# piezo-driver_v0_9b-R001.net
KiCad netlist of a schematic drawn in EAGLE
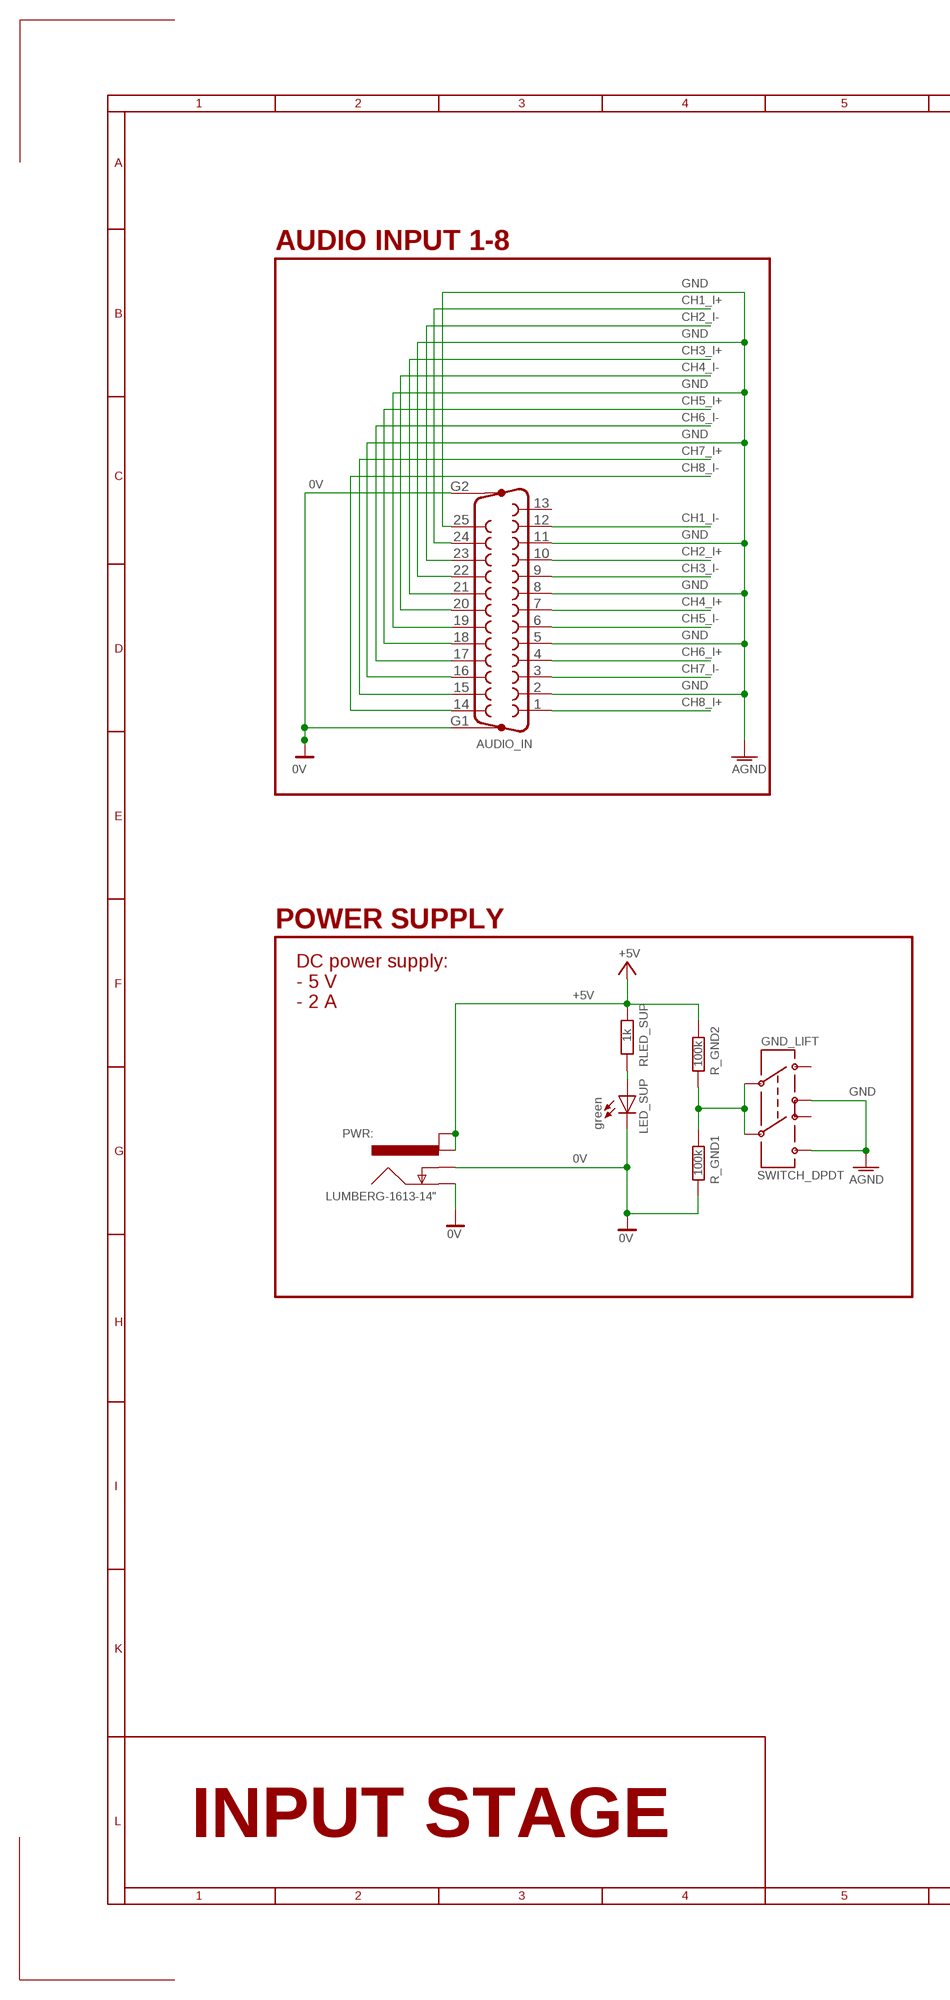
[diagram p0: schematic, sheet 1, part 1 of 2]
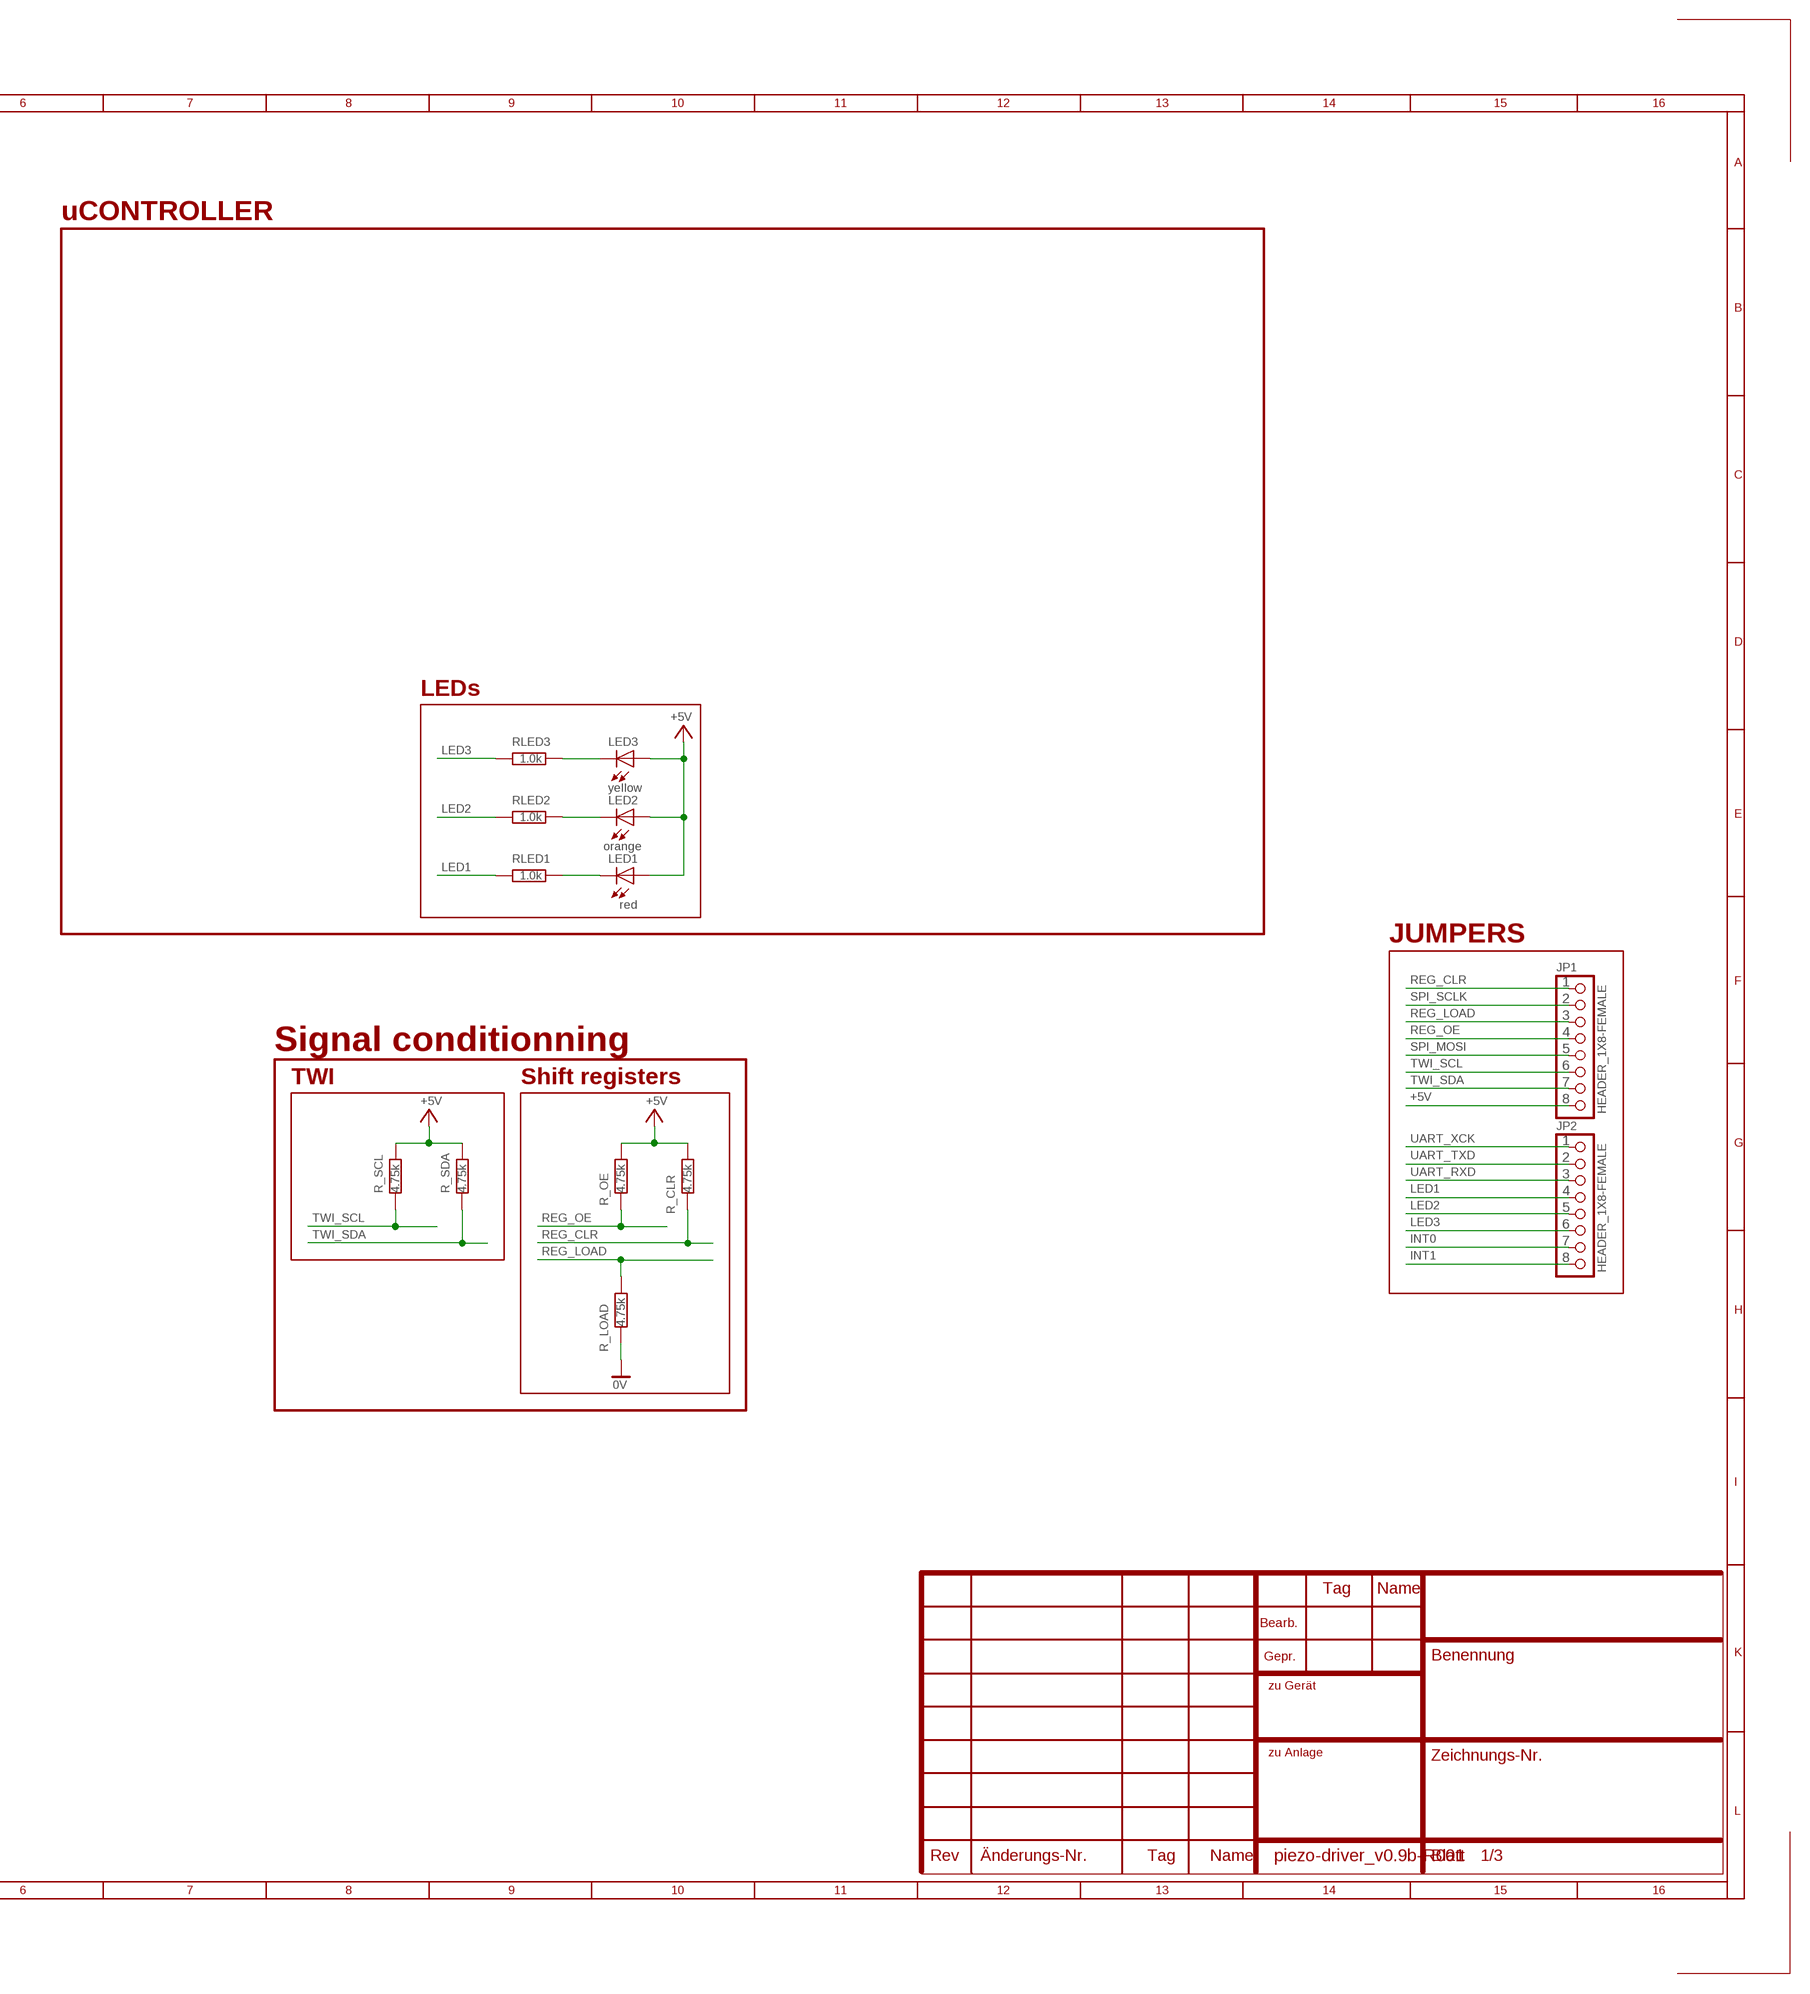
[diagram p1: schematic, sheet 1, part 2 of 2]
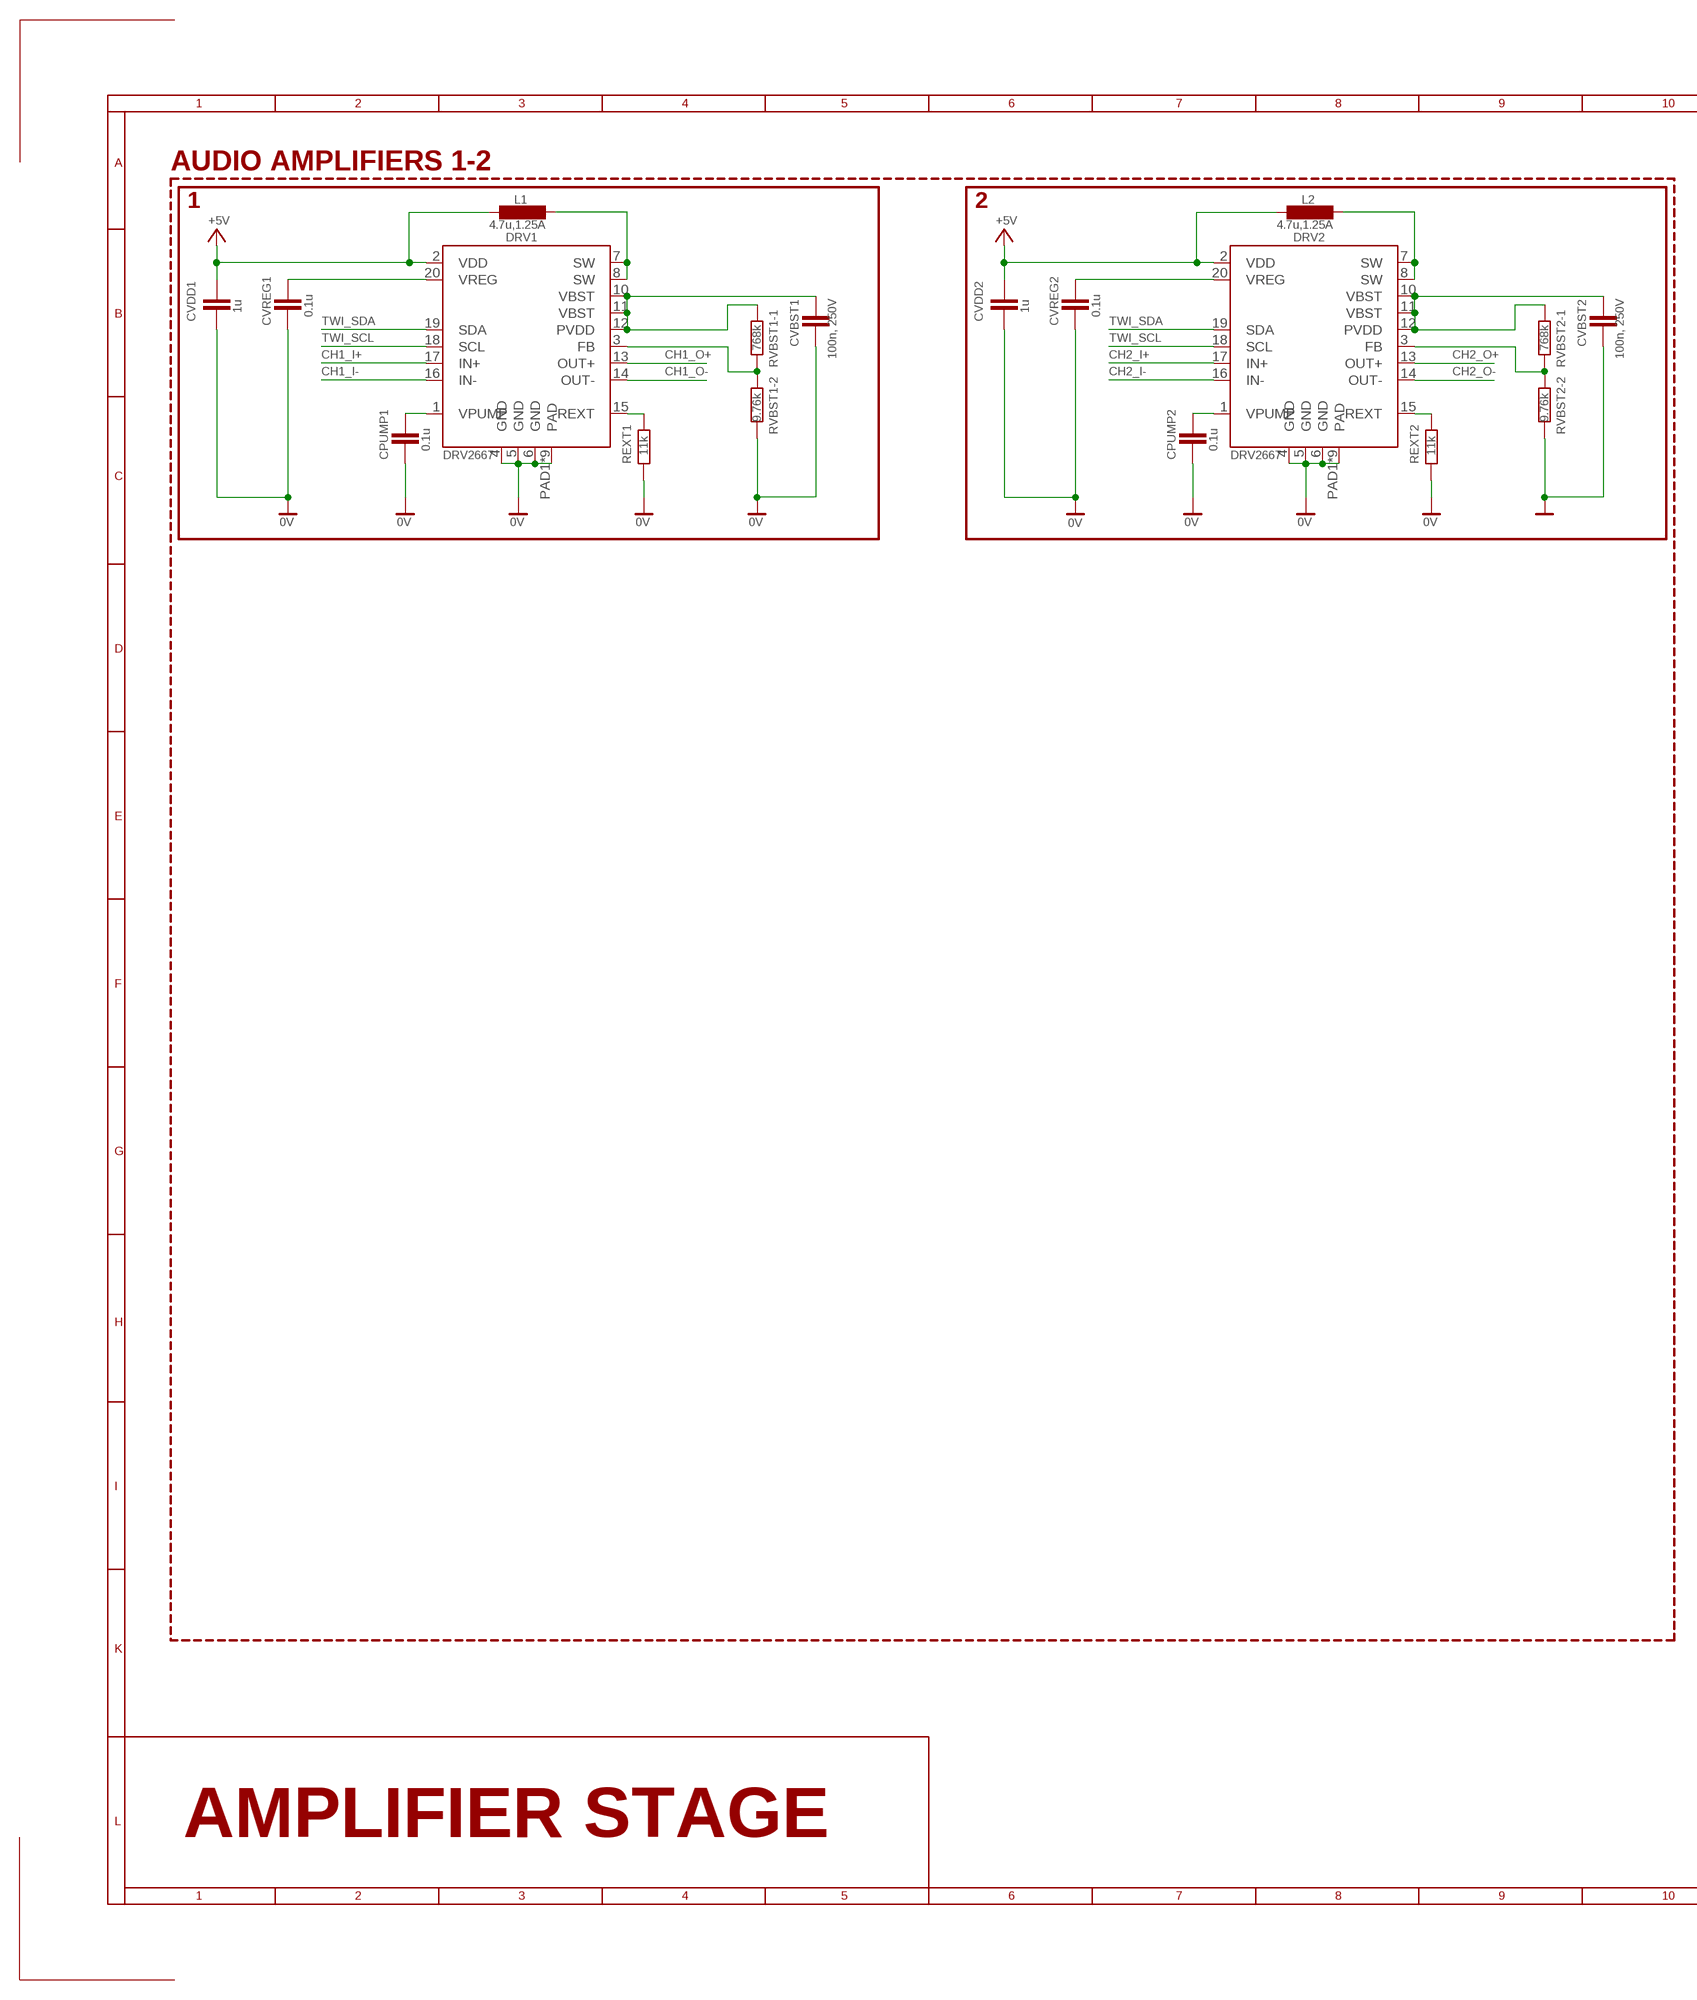
[diagram p2: schematic, sheet 2, part 1 of 2]
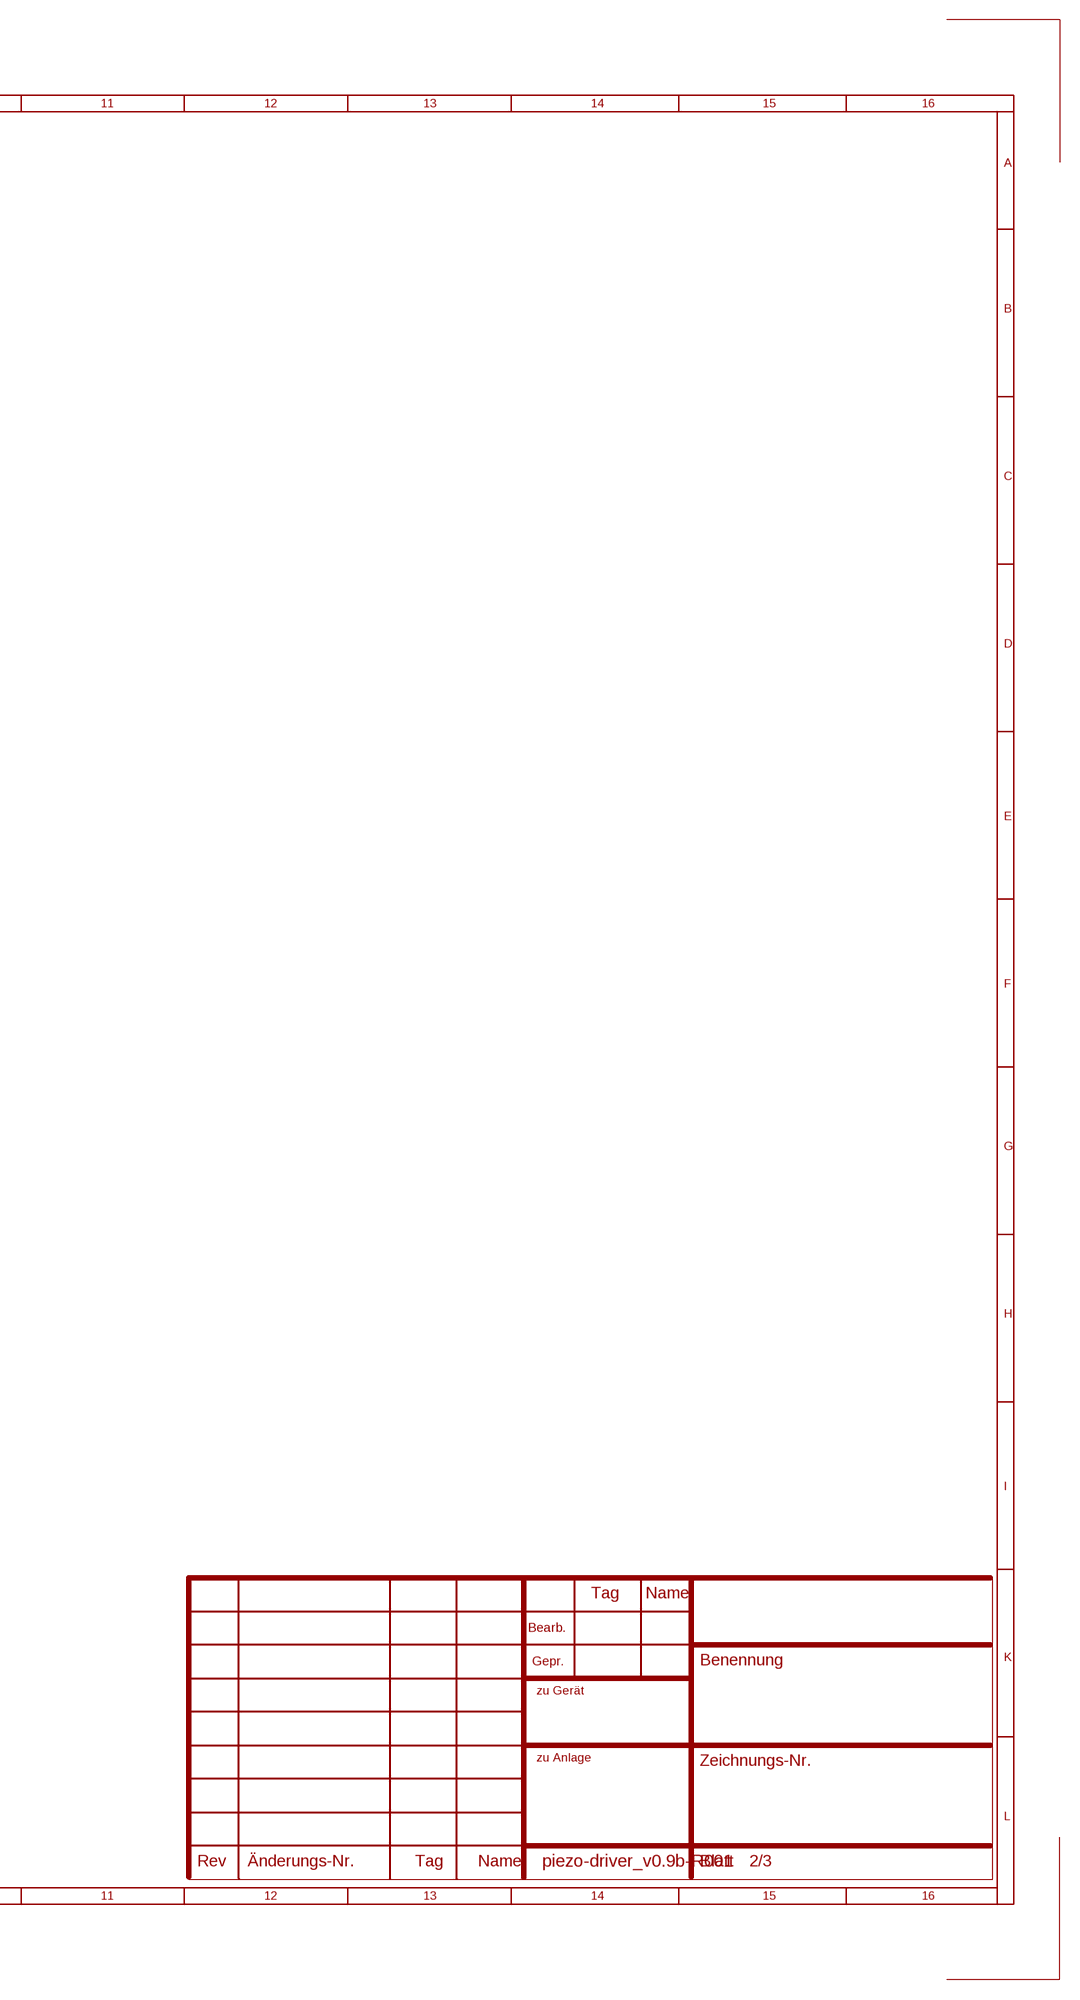
[diagram p3: schematic, sheet 2, part 2 of 2]
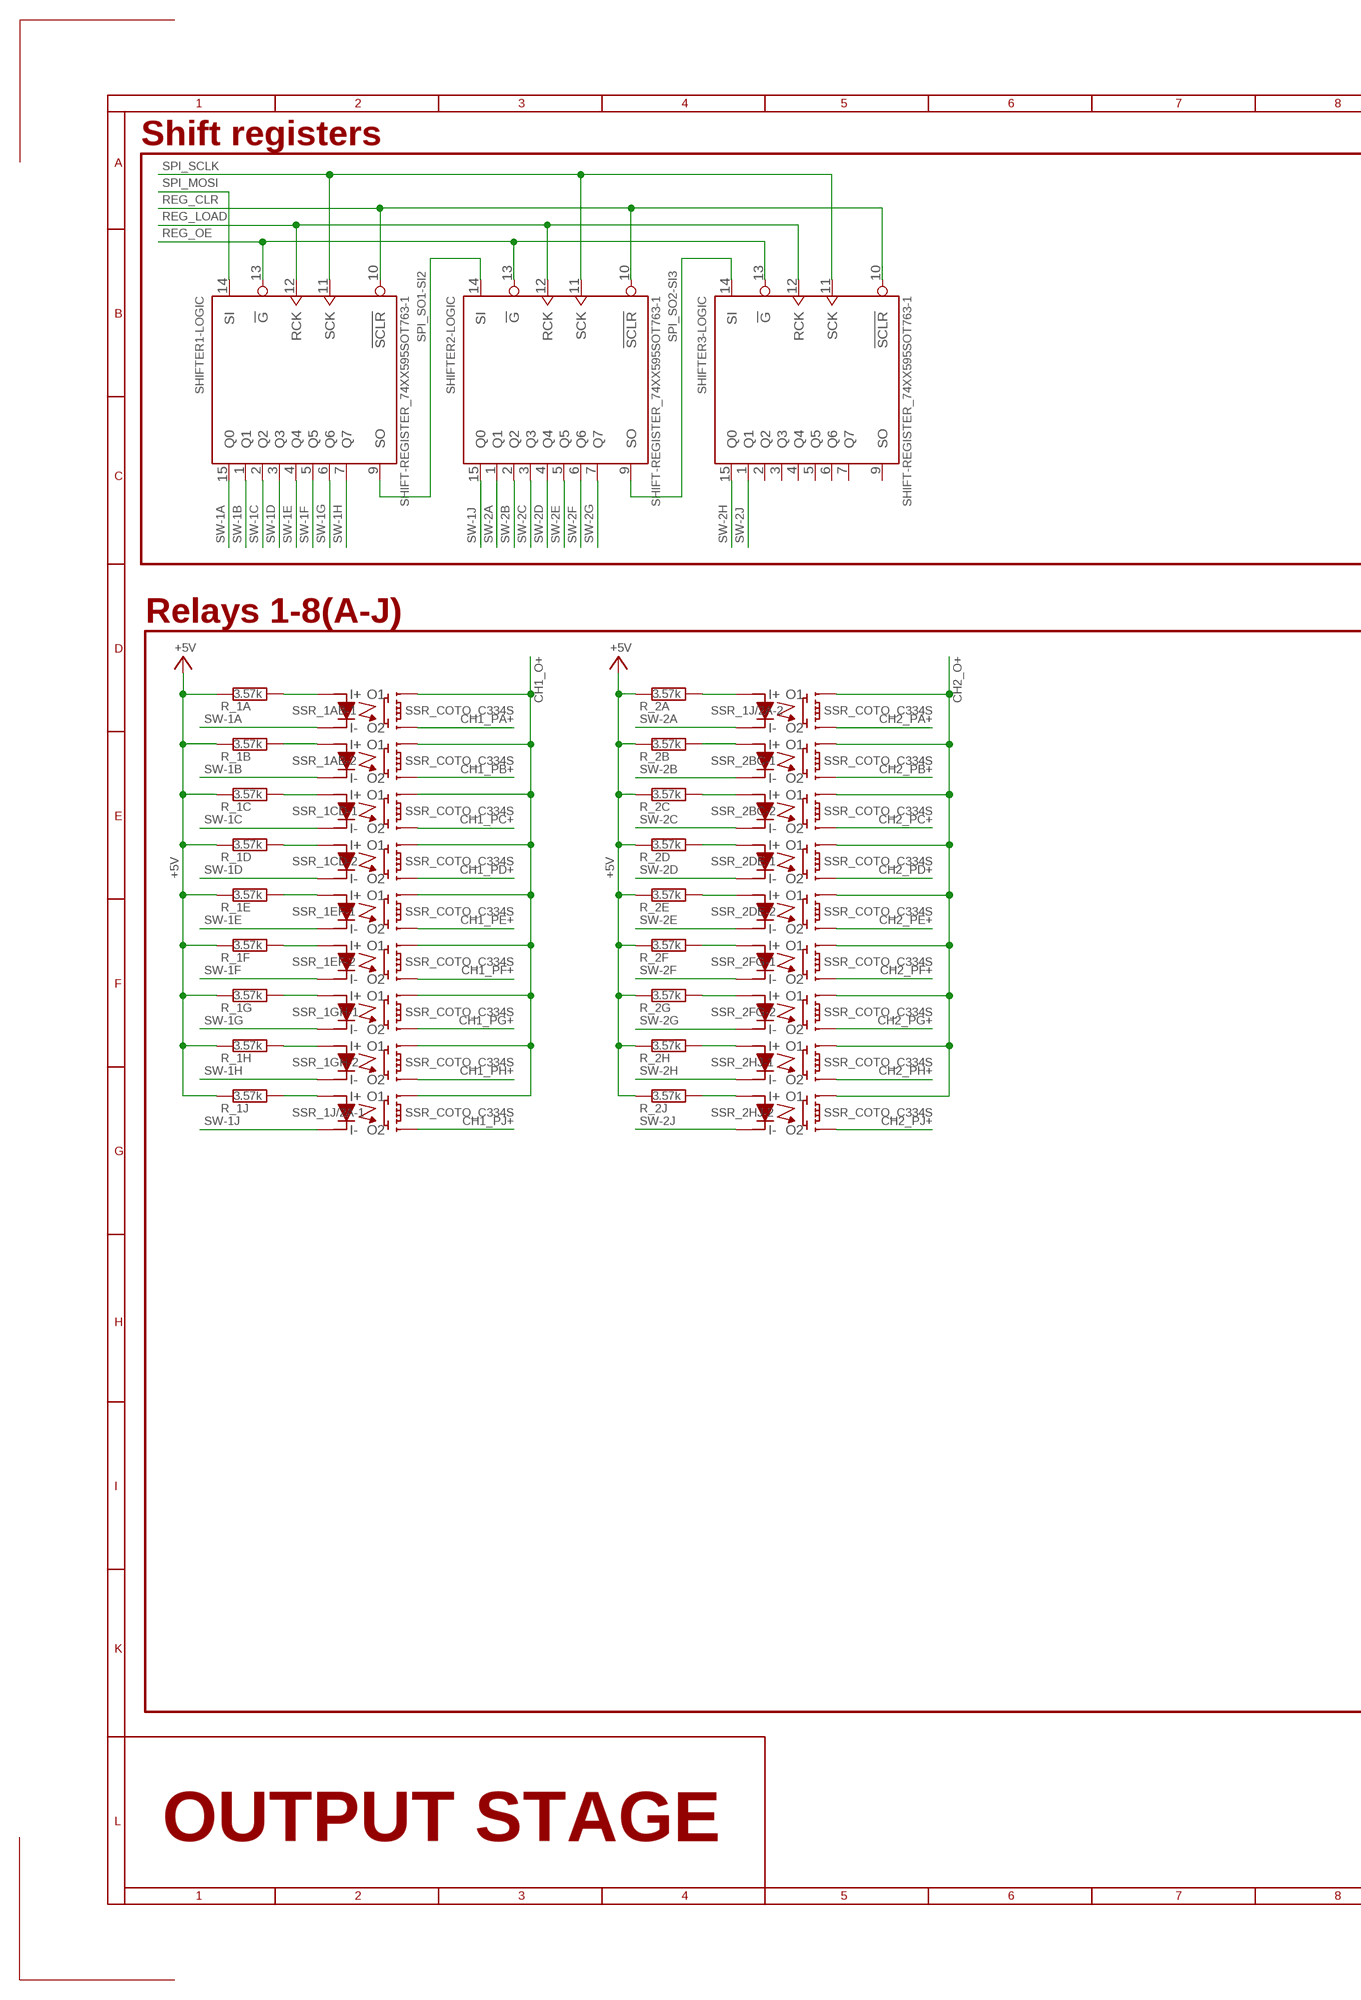
[diagram p4: schematic, sheet 3, part 1 of 2]
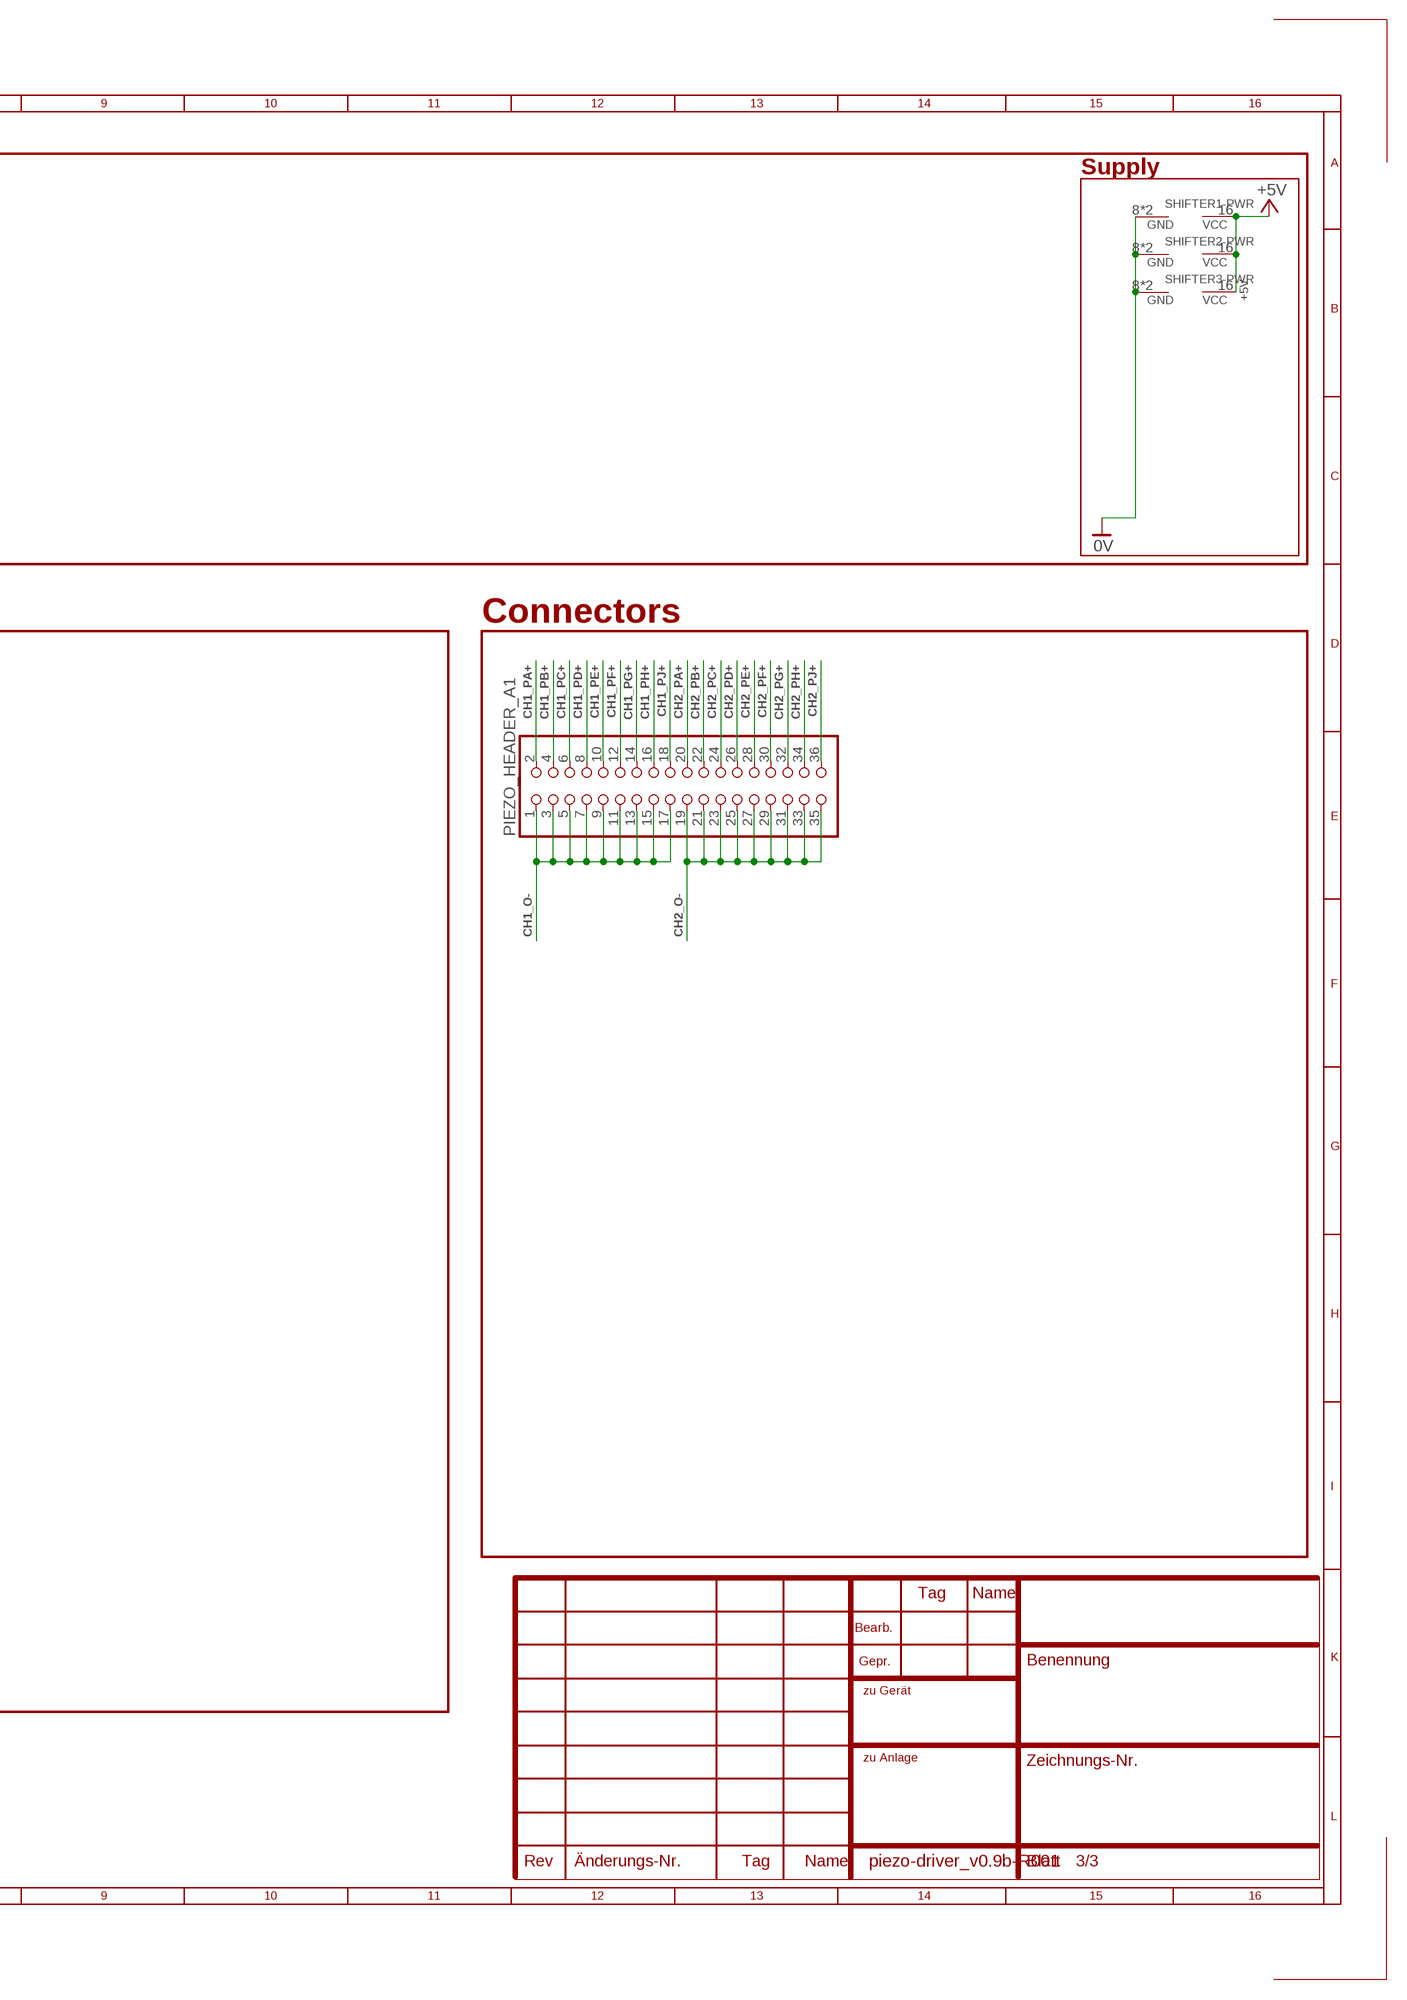
[diagram p5: schematic, sheet 3, part 2 of 2]

(export (version "E")
  (design (tool "Eeschema 10.0.6"))
  (components
    (comp (ref "CPUMP1")
      (value "0.1u")
      (footprint "eagle-import:C0402")
      (libsource (lib "eagle-import") (part "C-EUC0402"))
    )
    (comp (ref "CPUMP2")
      (value "0.1u")
      (footprint "eagle-import:C0402")
      (libsource (lib "eagle-import") (part "C-EUC0402"))
    )
    (comp (ref "CVBST1")
      (value "100n, 250V")
      (footprint "eagle-import:C0805")
      (libsource (lib "eagle-import") (part "C-EUC0805"))
    )
    (comp (ref "CVBST2")
      (value "100n, 250V")
      (footprint "eagle-import:C0805")
      (libsource (lib "eagle-import") (part "C-EUC0805"))
    )
    (comp (ref "CVDD1")
      (value "1u")
      (footprint "eagle-import:C0402")
      (libsource (lib "eagle-import") (part "C-EUC0402"))
    )
    (comp (ref "CVDD2")
      (value "1u")
      (footprint "eagle-import:C0402")
      (libsource (lib "eagle-import") (part "C-EUC0402"))
    )
    (comp (ref "CVREG1")
      (value "0.1u")
      (footprint "eagle-import:C0402")
      (libsource (lib "eagle-import") (part "C-EUC0402"))
    )
    (comp (ref "CVREG2")
      (value "0.1u")
      (footprint "eagle-import:C0402")
      (libsource (lib "eagle-import") (part "C-EUC0402"))
    )
    (comp (ref "DRV1")
      (value "DRV2667")
      (footprint "eagle-import:QFN-20_9TH")
      (libsource (lib "eagle-import") (part "DRV2667"))
    )
    (comp (ref "DRV2")
      (value "DRV2667")
      (footprint "eagle-import:QFN-20_9TH")
      (libsource (lib "eagle-import") (part "DRV2667"))
    )
    (comp (ref "L1")
      (value "4.7u,1.25A")
      (footprint "eagle-import:L3030")
      (libsource (lib "eagle-import") (part "L-EUL3030"))
    )
    (comp (ref "L2")
      (value "4.7u,1.25A")
      (footprint "eagle-import:L3030")
      (libsource (lib "eagle-import") (part "L-EUL3030"))
    )
    (comp (ref "REXT1")
      (value "11k")
      (footprint "eagle-import:R0402")
      (libsource (lib "eagle-import") (part "R-EU_R0402"))
    )
    (comp (ref "REXT2")
      (value "11k")
      (footprint "eagle-import:R0402")
      (libsource (lib "eagle-import") (part "R-EU_R0402"))
    )
    (comp (ref "RVBST1-1")
      (value "768k")
      (footprint "eagle-import:R0402")
      (libsource (lib "eagle-import") (part "R-EU_R0402"))
    )
    (comp (ref "RVBST1-2")
      (value "9.76k")
      (footprint "eagle-import:R0402")
      (libsource (lib "eagle-import") (part "R-EU_R0402"))
    )
    (comp (ref "RVBST2-1")
      (value "768k")
      (footprint "eagle-import:R0402")
      (libsource (lib "eagle-import") (part "R-EU_R0402"))
    )
    (comp (ref "RVBST2-2")
      (value "9.76k")
      (footprint "eagle-import:R0402")
      (libsource (lib "eagle-import") (part "R-EU_R0402"))
    )
    (comp (ref "AUDIO_IN")
      (value "F25HP")
      (footprint "eagle-import:F25HP")
      (libsource (lib "eagle-import") (part "F25HP"))
    )
    (comp (ref "GND_LIFT")
      (value "SWITCH_DPDT")
      (footprint "eagle-import:SWITCH_JS202011")
      (libsource (lib "eagle-import") (part "SWITCH_DPDT"))
    )
    (comp (ref "JP1")
      (value "HEADER_1X8-FEMALE")
      (footprint "eagle-import:1X08_2.54")
      (libsource (lib "eagle-import") (part "HEADER_1X8-FEMALE"))
    )
    (comp (ref "JP2")
      (value "HEADER_1X8-FEMALE")
      (footprint "eagle-import:1X08_2.54")
      (libsource (lib "eagle-import") (part "HEADER_1X8-FEMALE"))
    )
    (comp (ref "LED1")
      (value "red")
      (footprint "eagle-import:LED-1206")
      (libsource (lib "eagle-import") (part "LED1206"))
    )
    (comp (ref "LED2")
      (value "orange")
      (footprint "eagle-import:LED-1206")
      (libsource (lib "eagle-import") (part "LED1206"))
    )
    (comp (ref "LED3")
      (value "yellow")
      (footprint "eagle-import:LED-1206")
      (libsource (lib "eagle-import") (part "LED1206"))
    )
    (comp (ref "LED_SUP")
      (value "green")
      (footprint "eagle-import:LED-1206")
      (libsource (lib "eagle-import") (part "LED1206"))
    )
    (comp (ref "PWR:")
      (value "LUMBERG-1613-14\"")
      (footprint "eagle-import:LUMBERG-1613_14")
      (libsource (lib "eagle-import") (part "LUMBERG-1613-14{dblquote}"))
    )
    (comp (ref "RLED1")
      (value "1.0k")
      (footprint "eagle-import:R0402")
      (libsource (lib "eagle-import") (part "R-EU_R0402"))
    )
    (comp (ref "RLED2")
      (value "1.0k")
      (footprint "eagle-import:R0402")
      (libsource (lib "eagle-import") (part "R-EU_R0402"))
    )
    (comp (ref "RLED3")
      (value "1.0k")
      (footprint "eagle-import:R0402")
      (libsource (lib "eagle-import") (part "R-EU_R0402"))
    )
    (comp (ref "RLED_SUP")
      (value "1k")
      (footprint "eagle-import:R0402")
      (libsource (lib "eagle-import") (part "R-EU_R0402"))
    )
    (comp (ref "R_CLR")
      (value "4.75k")
      (footprint "eagle-import:R0402")
      (libsource (lib "eagle-import") (part "R-EU_R0402"))
    )
    (comp (ref "R_GND1")
      (value "100k")
      (footprint "eagle-import:R0402")
      (libsource (lib "eagle-import") (part "R-EU_R0402"))
    )
    (comp (ref "R_GND2")
      (value "100k")
      (footprint "eagle-import:R0402")
      (libsource (lib "eagle-import") (part "R-EU_R0402"))
    )
    (comp (ref "R_LOAD")
      (value "4.75k")
      (footprint "eagle-import:R0402")
      (libsource (lib "eagle-import") (part "R-EU_R0402"))
    )
    (comp (ref "R_OE")
      (value "4.75k")
      (footprint "eagle-import:R0402")
      (libsource (lib "eagle-import") (part "R-EU_R0402"))
    )
    (comp (ref "R_SCL")
      (value "4.75k")
      (footprint "eagle-import:R0402")
      (libsource (lib "eagle-import") (part "R-EU_R0402"))
    )
    (comp (ref "R_SDA")
      (value "4.75k")
      (footprint "eagle-import:R0402")
      (libsource (lib "eagle-import") (part "R-EU_R0402"))
    )
    (comp (ref "PIEZO_HEADER_A1")
      (value "PINHD-2X18")
      (footprint "eagle-import:2X18")
      (libsource (lib "eagle-import") (part "PINHD-2X18"))
    )
    (comp (ref "R_1A")
      (value "3.57k")
      (footprint "eagle-import:R0402")
      (libsource (lib "eagle-import") (part "R-EU_R0402"))
    )
    (comp (ref "R_1B")
      (value "3.57k")
      (footprint "eagle-import:R0402")
      (libsource (lib "eagle-import") (part "R-EU_R0402"))
    )
    (comp (ref "R_1C")
      (value "3.57k")
      (footprint "eagle-import:R0402")
      (libsource (lib "eagle-import") (part "R-EU_R0402"))
    )
    (comp (ref "R_1D")
      (value "3.57k")
      (footprint "eagle-import:R0402")
      (libsource (lib "eagle-import") (part "R-EU_R0402"))
    )
    (comp (ref "R_1E")
      (value "3.57k")
      (footprint "eagle-import:R0402")
      (libsource (lib "eagle-import") (part "R-EU_R0402"))
    )
    (comp (ref "R_1F")
      (value "3.57k")
      (footprint "eagle-import:R0402")
      (libsource (lib "eagle-import") (part "R-EU_R0402"))
    )
    (comp (ref "R_1G")
      (value "3.57k")
      (footprint "eagle-import:R0402")
      (libsource (lib "eagle-import") (part "R-EU_R0402"))
    )
    (comp (ref "R_1H")
      (value "3.57k")
      (footprint "eagle-import:R0402")
      (libsource (lib "eagle-import") (part "R-EU_R0402"))
    )
    (comp (ref "R_1J")
      (value "3.57k")
      (footprint "eagle-import:R0402")
      (libsource (lib "eagle-import") (part "R-EU_R0402"))
    )
    (comp (ref "R_2A")
      (value "3.57k")
      (footprint "eagle-import:R0402")
      (libsource (lib "eagle-import") (part "R-EU_R0402"))
    )
    (comp (ref "R_2B")
      (value "3.57k")
      (footprint "eagle-import:R0402")
      (libsource (lib "eagle-import") (part "R-EU_R0402"))
    )
    (comp (ref "R_2C")
      (value "3.57k")
      (footprint "eagle-import:R0402")
      (libsource (lib "eagle-import") (part "R-EU_R0402"))
    )
    (comp (ref "R_2D")
      (value "3.57k")
      (footprint "eagle-import:R0402")
      (libsource (lib "eagle-import") (part "R-EU_R0402"))
    )
    (comp (ref "R_2E")
      (value "3.57k")
      (footprint "eagle-import:R0402")
      (libsource (lib "eagle-import") (part "R-EU_R0402"))
    )
    (comp (ref "R_2F")
      (value "3.57k")
      (footprint "eagle-import:R0402")
      (libsource (lib "eagle-import") (part "R-EU_R0402"))
    )
    (comp (ref "R_2G")
      (value "3.57k")
      (footprint "eagle-import:R0402")
      (libsource (lib "eagle-import") (part "R-EU_R0402"))
    )
    (comp (ref "R_2H")
      (value "3.57k")
      (footprint "eagle-import:R0402")
      (libsource (lib "eagle-import") (part "R-EU_R0402"))
    )
    (comp (ref "R_2J")
      (value "3.57k")
      (footprint "eagle-import:R0402")
      (libsource (lib "eagle-import") (part "R-EU_R0402"))
    )
    (comp (ref "SHIFTER1")
      (value "SHIFT-REGISTER_74XX595SOT763-1")
      (footprint "eagle-import:SOT763-1")
      (libsource (lib "eagle-import") (part "SHIFT-REGISTER_74XX595SOT763-1"))
    )
    (comp (ref "SHIFTER2")
      (value "SHIFT-REGISTER_74XX595SOT763-1")
      (footprint "eagle-import:SOT763-1")
      (libsource (lib "eagle-import") (part "SHIFT-REGISTER_74XX595SOT763-1"))
    )
    (comp (ref "SHIFTER3")
      (value "SHIFT-REGISTER_74XX595SOT763-1")
      (footprint "eagle-import:SOT763-1")
      (libsource (lib "eagle-import") (part "SHIFT-REGISTER_74XX595SOT763-1"))
    )
    (comp (ref "SSR_1AB")
      (value "SSR_COTO_C334S")
      (footprint "eagle-import:SOP8")
      (libsource (lib "eagle-import") (part "SSR_COTO_C334S"))
    )
    (comp (ref "SSR_1CD")
      (value "SSR_COTO_C334S")
      (footprint "eagle-import:SOP8")
      (libsource (lib "eagle-import") (part "SSR_COTO_C334S"))
    )
    (comp (ref "SSR_1EF")
      (value "SSR_COTO_C334S")
      (footprint "eagle-import:SOP8")
      (libsource (lib "eagle-import") (part "SSR_COTO_C334S"))
    )
    (comp (ref "SSR_1GH")
      (value "SSR_COTO_C334S")
      (footprint "eagle-import:SOP8")
      (libsource (lib "eagle-import") (part "SSR_COTO_C334S"))
    )
    (comp (ref "SSR_1J/2A")
      (value "SSR_COTO_C334S")
      (footprint "eagle-import:SOP8")
      (libsource (lib "eagle-import") (part "SSR_COTO_C334S"))
    )
    (comp (ref "SSR_2BC")
      (value "SSR_COTO_C334S")
      (footprint "eagle-import:SOP8")
      (libsource (lib "eagle-import") (part "SSR_COTO_C334S"))
    )
    (comp (ref "SSR_2DE")
      (value "SSR_COTO_C334S")
      (footprint "eagle-import:SOP8")
      (libsource (lib "eagle-import") (part "SSR_COTO_C334S"))
    )
    (comp (ref "SSR_2FG")
      (value "SSR_COTO_C334S")
      (footprint "eagle-import:SOP8")
      (libsource (lib "eagle-import") (part "SSR_COTO_C334S"))
    )
    (comp (ref "SSR_2HJ")
      (value "SSR_COTO_C334S")
      (footprint "eagle-import:SOP8")
      (libsource (lib "eagle-import") (part "SSR_COTO_C334S"))
    )
  )
  (nets
    (net (code "1") (name "+5V") (class "Default")
      (node (ref "CVDD1") (pin "1") (pinfunction "1_1") (pintype "passive"))
      (node (ref "CVDD2") (pin "1") (pinfunction "1_1") (pintype "passive"))
      (node (ref "DRV1") (pin "2") (pinfunction "VDD_2") (pintype "bidirectional"))
      (node (ref "DRV2") (pin "2") (pinfunction "VDD_2") (pintype "bidirectional"))
      (node (ref "JP1") (pin "8") (pinfunction "8_8") (pintype "passive"))
      (node (ref "L1") (pin "2") (pinfunction "2_2") (pintype "passive"))
      (node (ref "L2") (pin "2") (pinfunction "2_2") (pintype "passive"))
      (node (ref "LED1") (pin "A") (pinfunction "A_A") (pintype "passive"))
      (node (ref "LED2") (pin "A") (pinfunction "A_A") (pintype "passive"))
      (node (ref "LED3") (pin "A") (pinfunction "A_A") (pintype "passive"))
      (node (ref "PWR:") (pin "3") (pinfunction "PWR_1_3") (pintype "power_in"))
      (node (ref "PWR:") (pin "4") (pinfunction "PWR_2_4") (pintype "power_in"))
      (node (ref "RLED_SUP") (pin "2") (pinfunction "2_2") (pintype "passive"))
      (node (ref "R_1A") (pin "2") (pinfunction "2_2") (pintype "passive"))
      (node (ref "R_1B") (pin "2") (pinfunction "2_2") (pintype "passive"))
      (node (ref "R_1C") (pin "2") (pinfunction "2_2") (pintype "passive"))
      (node (ref "R_1D") (pin "2") (pinfunction "2_2") (pintype "passive"))
      (node (ref "R_1E") (pin "2") (pinfunction "2_2") (pintype "passive"))
      (node (ref "R_1F") (pin "2") (pinfunction "2_2") (pintype "passive"))
      (node (ref "R_1G") (pin "2") (pinfunction "2_2") (pintype "passive"))
      (node (ref "R_1H") (pin "2") (pinfunction "2_2") (pintype "passive"))
      (node (ref "R_1J") (pin "2") (pinfunction "2_2") (pintype "passive"))
      (node (ref "R_2A") (pin "2") (pinfunction "2_2") (pintype "passive"))
      (node (ref "R_2B") (pin "2") (pinfunction "2_2") (pintype "passive"))
      (node (ref "R_2C") (pin "2") (pinfunction "2_2") (pintype "passive"))
      (node (ref "R_2D") (pin "2") (pinfunction "2_2") (pintype "passive"))
      (node (ref "R_2E") (pin "2") (pinfunction "2_2") (pintype "passive"))
      (node (ref "R_2F") (pin "2") (pinfunction "2_2") (pintype "passive"))
      (node (ref "R_2G") (pin "2") (pinfunction "2_2") (pintype "passive"))
      (node (ref "R_2H") (pin "2") (pinfunction "2_2") (pintype "passive"))
      (node (ref "R_2J") (pin "2") (pinfunction "2_2") (pintype "passive"))
      (node (ref "R_CLR") (pin "2") (pinfunction "2_2") (pintype "passive"))
      (node (ref "R_GND2") (pin "2") (pinfunction "2_2") (pintype "passive"))
      (node (ref "R_OE") (pin "2") (pinfunction "2_2") (pintype "passive"))
      (node (ref "R_SCL") (pin "2") (pinfunction "2_2") (pintype "passive"))
      (node (ref "R_SDA") (pin "2") (pinfunction "2_2") (pintype "passive"))
      (node (ref "SHIFTER1") (pin "16") (pinfunction "VCC_16") (pintype "power_in"))
      (node (ref "SHIFTER2") (pin "16") (pinfunction "VCC_16") (pintype "power_in"))
      (node (ref "SHIFTER3") (pin "16") (pinfunction "VCC_16") (pintype "power_in"))
    )
    (net (code "2") (name "0V") (class "Default")
      (node (ref "AUDIO_IN") (pin "G1") (pinfunction "G1_G1") (pintype "passive"))
      (node (ref "AUDIO_IN") (pin "G2") (pinfunction "G2_G2") (pintype "passive"))
      (node (ref "CPUMP1") (pin "2") (pinfunction "2_2") (pintype "passive"))
      (node (ref "CPUMP2") (pin "2") (pinfunction "2_2") (pintype "passive"))
      (node (ref "CVBST1") (pin "2") (pinfunction "2_2") (pintype "passive"))
      (node (ref "CVBST2") (pin "2") (pinfunction "2_2") (pintype "passive"))
      (node (ref "CVDD1") (pin "2") (pinfunction "2_2") (pintype "passive"))
      (node (ref "CVDD2") (pin "2") (pinfunction "2_2") (pintype "passive"))
      (node (ref "CVREG1") (pin "2") (pinfunction "2_2") (pintype "passive"))
      (node (ref "CVREG2") (pin "2") (pinfunction "2_2") (pintype "passive"))
      (node (ref "DRV1") (pin "4") (pinfunction "GND_4") (pintype "bidirectional"))
      (node (ref "DRV1") (pin "5") (pinfunction "GND_5") (pintype "bidirectional"))
      (node (ref "DRV1") (pin "6") (pinfunction "GND_6") (pintype "bidirectional"))
      (node (ref "DRV1") (pin "PAD1") (pinfunction "PAD_PAD1") (pintype "bidirectional"))
      (node (ref "DRV1") (pin "PAD2") (pinfunction "PAD_PAD2") (pintype "bidirectional"))
      (node (ref "DRV1") (pin "PAD3") (pinfunction "PAD_PAD3") (pintype "bidirectional"))
      (node (ref "DRV1") (pin "PAD4") (pinfunction "PAD_PAD4") (pintype "bidirectional"))
      (node (ref "DRV1") (pin "PAD5") (pinfunction "PAD_PAD5") (pintype "bidirectional"))
      (node (ref "DRV1") (pin "PAD6") (pinfunction "PAD_PAD6") (pintype "bidirectional"))
      (node (ref "DRV1") (pin "PAD7") (pinfunction "PAD_PAD7") (pintype "bidirectional"))
      (node (ref "DRV1") (pin "PAD8") (pinfunction "PAD_PAD8") (pintype "bidirectional"))
      (node (ref "DRV1") (pin "PAD9") (pinfunction "PAD_PAD9") (pintype "bidirectional"))
      (node (ref "DRV2") (pin "4") (pinfunction "GND_4") (pintype "bidirectional"))
      (node (ref "DRV2") (pin "5") (pinfunction "GND_5") (pintype "bidirectional"))
      (node (ref "DRV2") (pin "6") (pinfunction "GND_6") (pintype "bidirectional"))
      (node (ref "DRV2") (pin "PAD1") (pinfunction "PAD_PAD1") (pintype "bidirectional"))
      (node (ref "DRV2") (pin "PAD2") (pinfunction "PAD_PAD2") (pintype "bidirectional"))
      (node (ref "DRV2") (pin "PAD3") (pinfunction "PAD_PAD3") (pintype "bidirectional"))
      (node (ref "DRV2") (pin "PAD4") (pinfunction "PAD_PAD4") (pintype "bidirectional"))
      (node (ref "DRV2") (pin "PAD5") (pinfunction "PAD_PAD5") (pintype "bidirectional"))
      (node (ref "DRV2") (pin "PAD6") (pinfunction "PAD_PAD6") (pintype "bidirectional"))
      (node (ref "DRV2") (pin "PAD7") (pinfunction "PAD_PAD7") (pintype "bidirectional"))
      (node (ref "DRV2") (pin "PAD8") (pinfunction "PAD_PAD8") (pintype "bidirectional"))
      (node (ref "DRV2") (pin "PAD9") (pinfunction "PAD_PAD9") (pintype "bidirectional"))
      (node (ref "LED_SUP") (pin "C") (pinfunction "C_C") (pintype "passive"))
      (node (ref "PWR:") (pin "1") (pinfunction "GND_1") (pintype "power_in"))
      (node (ref "PWR:") (pin "2") (pinfunction "GND_INS_2") (pintype "power_in"))
      (node (ref "REXT1") (pin "1") (pinfunction "1_1") (pintype "passive"))
      (node (ref "REXT2") (pin "1") (pinfunction "1_1") (pintype "passive"))
      (node (ref "RVBST1-2") (pin "1") (pinfunction "1_1") (pintype "passive"))
      (node (ref "RVBST2-2") (pin "1") (pinfunction "1_1") (pintype "passive"))
      (node (ref "R_GND1") (pin "1") (pinfunction "1_1") (pintype "passive"))
      (node (ref "R_LOAD") (pin "1") (pinfunction "1_1") (pintype "passive"))
      (node (ref "SHIFTER1") (pin "8") (pinfunction "GND_8") (pintype "power_in"))
      (node (ref "SHIFTER1") (pin "PAD") (pinfunction "GND_PAD") (pintype "power_in"))
      (node (ref "SHIFTER2") (pin "8") (pinfunction "GND_8") (pintype "power_in"))
      (node (ref "SHIFTER2") (pin "PAD") (pinfunction "GND_PAD") (pintype "power_in"))
      (node (ref "SHIFTER3") (pin "8") (pinfunction "GND_8") (pintype "power_in"))
      (node (ref "SHIFTER3") (pin "PAD") (pinfunction "GND_PAD") (pintype "power_in"))
    )
    (net (code "3") (name "CH1_I+") (class "Default")
      (node (ref "AUDIO_IN") (pin "24") (pinfunction "24_24") (pintype "passive"))
      (node (ref "DRV1") (pin "17") (pinfunction "IN+_17") (pintype "bidirectional"))
    )
    (net (code "4") (name "CH1_I-") (class "Default")
      (node (ref "AUDIO_IN") (pin "12") (pinfunction "12_12") (pintype "passive"))
      (node (ref "DRV1") (pin "16") (pinfunction "IN-_16") (pintype "bidirectional"))
    )
    (net (code "5") (name "CH1_O+") (class "Default")
      (node (ref "DRV1") (pin "13") (pinfunction "OUT+_13") (pintype "bidirectional"))
      (node (ref "SSR_1AB") (pin "5") (pinfunction "O1_5") (pintype "bidirectional"))
      (node (ref "SSR_1AB") (pin "7") (pinfunction "O1_7") (pintype "bidirectional"))
      (node (ref "SSR_1CD") (pin "5") (pinfunction "O1_5") (pintype "bidirectional"))
      (node (ref "SSR_1CD") (pin "7") (pinfunction "O1_7") (pintype "bidirectional"))
      (node (ref "SSR_1EF") (pin "5") (pinfunction "O1_5") (pintype "bidirectional"))
      (node (ref "SSR_1EF") (pin "7") (pinfunction "O1_7") (pintype "bidirectional"))
      (node (ref "SSR_1GH") (pin "5") (pinfunction "O1_5") (pintype "bidirectional"))
      (node (ref "SSR_1GH") (pin "7") (pinfunction "O1_7") (pintype "bidirectional"))
      (node (ref "SSR_1J/2A") (pin "7") (pinfunction "O1_7") (pintype "bidirectional"))
    )
    (net (code "6") (name "CH1_O-") (class "Default")
      (node (ref "DRV1") (pin "14") (pinfunction "OUT-_14") (pintype "bidirectional"))
      (node (ref "PIEZO_HEADER_A1") (pin "1") (pinfunction "1_1") (pintype "passive"))
      (node (ref "PIEZO_HEADER_A1") (pin "11") (pinfunction "11_11") (pintype "passive"))
      (node (ref "PIEZO_HEADER_A1") (pin "13") (pinfunction "13_13") (pintype "passive"))
      (node (ref "PIEZO_HEADER_A1") (pin "15") (pinfunction "15_15") (pintype "passive"))
      (node (ref "PIEZO_HEADER_A1") (pin "17") (pinfunction "17_17") (pintype "passive"))
      (node (ref "PIEZO_HEADER_A1") (pin "3") (pinfunction "3_3") (pintype "passive"))
      (node (ref "PIEZO_HEADER_A1") (pin "5") (pinfunction "5_5") (pintype "passive"))
      (node (ref "PIEZO_HEADER_A1") (pin "7") (pinfunction "7_7") (pintype "passive"))
      (node (ref "PIEZO_HEADER_A1") (pin "9") (pinfunction "9_9") (pintype "passive"))
    )
    (net (code "7") (name "CH1_PA+") (class "Default")
      (node (ref "PIEZO_HEADER_A1") (pin "2") (pinfunction "2_2") (pintype "passive"))
      (node (ref "SSR_1AB") (pin "8") (pinfunction "O2_8") (pintype "bidirectional"))
    )
    (net (code "8") (name "CH1_PB+") (class "Default")
      (node (ref "PIEZO_HEADER_A1") (pin "4") (pinfunction "4_4") (pintype "passive"))
      (node (ref "SSR_1AB") (pin "6") (pinfunction "O2_6") (pintype "bidirectional"))
    )
    (net (code "9") (name "CH1_PC+") (class "Default")
      (node (ref "PIEZO_HEADER_A1") (pin "6") (pinfunction "6_6") (pintype "passive"))
      (node (ref "SSR_1CD") (pin "8") (pinfunction "O2_8") (pintype "bidirectional"))
    )
    (net (code "10") (name "CH1_PD+") (class "Default")
      (node (ref "PIEZO_HEADER_A1") (pin "8") (pinfunction "8_8") (pintype "passive"))
      (node (ref "SSR_1CD") (pin "6") (pinfunction "O2_6") (pintype "bidirectional"))
    )
    (net (code "11") (name "CH1_PE+") (class "Default")
      (node (ref "PIEZO_HEADER_A1") (pin "10") (pinfunction "10_10") (pintype "passive"))
      (node (ref "SSR_1EF") (pin "8") (pinfunction "O2_8") (pintype "bidirectional"))
    )
    (net (code "12") (name "CH1_PF+") (class "Default")
      (node (ref "PIEZO_HEADER_A1") (pin "12") (pinfunction "12_12") (pintype "passive"))
      (node (ref "SSR_1EF") (pin "6") (pinfunction "O2_6") (pintype "bidirectional"))
    )
    (net (code "13") (name "CH1_PG+") (class "Default")
      (node (ref "PIEZO_HEADER_A1") (pin "14") (pinfunction "14_14") (pintype "passive"))
      (node (ref "SSR_1GH") (pin "8") (pinfunction "O2_8") (pintype "bidirectional"))
    )
    (net (code "14") (name "CH1_PH+") (class "Default")
      (node (ref "PIEZO_HEADER_A1") (pin "16") (pinfunction "16_16") (pintype "passive"))
      (node (ref "SSR_1GH") (pin "6") (pinfunction "O2_6") (pintype "bidirectional"))
    )
    (net (code "15") (name "CH1_PJ+") (class "Default")
      (node (ref "PIEZO_HEADER_A1") (pin "18") (pinfunction "18_18") (pintype "passive"))
      (node (ref "SSR_1J/2A") (pin "8") (pinfunction "O2_8") (pintype "bidirectional"))
    )
    (net (code "16") (name "CH2_I+") (class "Default")
      (node (ref "AUDIO_IN") (pin "10") (pinfunction "10_10") (pintype "passive"))
      (node (ref "DRV2") (pin "17") (pinfunction "IN+_17") (pintype "bidirectional"))
    )
    (net (code "17") (name "CH2_I-") (class "Default")
      (node (ref "AUDIO_IN") (pin "23") (pinfunction "23_23") (pintype "passive"))
      (node (ref "DRV2") (pin "16") (pinfunction "IN-_16") (pintype "bidirectional"))
    )
    (net (code "18") (name "CH2_O+") (class "Default")
      (node (ref "DRV2") (pin "13") (pinfunction "OUT+_13") (pintype "bidirectional"))
      (node (ref "SSR_1J/2A") (pin "5") (pinfunction "O1_5") (pintype "bidirectional"))
      (node (ref "SSR_2BC") (pin "5") (pinfunction "O1_5") (pintype "bidirectional"))
      (node (ref "SSR_2BC") (pin "7") (pinfunction "O1_7") (pintype "bidirectional"))
      (node (ref "SSR_2DE") (pin "5") (pinfunction "O1_5") (pintype "bidirectional"))
      (node (ref "SSR_2DE") (pin "7") (pinfunction "O1_7") (pintype "bidirectional"))
      (node (ref "SSR_2FG") (pin "5") (pinfunction "O1_5") (pintype "bidirectional"))
      (node (ref "SSR_2FG") (pin "7") (pinfunction "O1_7") (pintype "bidirectional"))
      (node (ref "SSR_2HJ") (pin "5") (pinfunction "O1_5") (pintype "bidirectional"))
      (node (ref "SSR_2HJ") (pin "7") (pinfunction "O1_7") (pintype "bidirectional"))
    )
    (net (code "19") (name "CH2_O-") (class "Default")
      (node (ref "DRV2") (pin "14") (pinfunction "OUT-_14") (pintype "bidirectional"))
      (node (ref "PIEZO_HEADER_A1") (pin "19") (pinfunction "19_19") (pintype "passive"))
      (node (ref "PIEZO_HEADER_A1") (pin "21") (pinfunction "21_21") (pintype "passive"))
      (node (ref "PIEZO_HEADER_A1") (pin "23") (pinfunction "23_23") (pintype "passive"))
      (node (ref "PIEZO_HEADER_A1") (pin "25") (pinfunction "25_25") (pintype "passive"))
      (node (ref "PIEZO_HEADER_A1") (pin "27") (pinfunction "27_27") (pintype "passive"))
      (node (ref "PIEZO_HEADER_A1") (pin "29") (pinfunction "29_29") (pintype "passive"))
      (node (ref "PIEZO_HEADER_A1") (pin "31") (pinfunction "31_31") (pintype "passive"))
      (node (ref "PIEZO_HEADER_A1") (pin "33") (pinfunction "33_33") (pintype "passive"))
      (node (ref "PIEZO_HEADER_A1") (pin "35") (pinfunction "35_35") (pintype "passive"))
    )
    (net (code "20") (name "CH2_PA+") (class "Default")
      (node (ref "PIEZO_HEADER_A1") (pin "20") (pinfunction "20_20") (pintype "passive"))
      (node (ref "SSR_1J/2A") (pin "6") (pinfunction "O2_6") (pintype "bidirectional"))
    )
    (net (code "21") (name "CH2_PB+") (class "Default")
      (node (ref "PIEZO_HEADER_A1") (pin "22") (pinfunction "22_22") (pintype "passive"))
      (node (ref "SSR_2BC") (pin "8") (pinfunction "O2_8") (pintype "bidirectional"))
    )
    (net (code "22") (name "CH2_PC+") (class "Default")
      (node (ref "PIEZO_HEADER_A1") (pin "24") (pinfunction "24_24") (pintype "passive"))
      (node (ref "SSR_2BC") (pin "6") (pinfunction "O2_6") (pintype "bidirectional"))
    )
    (net (code "23") (name "CH2_PD+") (class "Default")
      (node (ref "PIEZO_HEADER_A1") (pin "26") (pinfunction "26_26") (pintype "passive"))
      (node (ref "SSR_2DE") (pin "8") (pinfunction "O2_8") (pintype "bidirectional"))
    )
    (net (code "24") (name "CH2_PE+") (class "Default")
      (node (ref "PIEZO_HEADER_A1") (pin "28") (pinfunction "28_28") (pintype "passive"))
      (node (ref "SSR_2DE") (pin "6") (pinfunction "O2_6") (pintype "bidirectional"))
    )
    (net (code "25") (name "CH2_PF+") (class "Default")
      (node (ref "PIEZO_HEADER_A1") (pin "30") (pinfunction "30_30") (pintype "passive"))
      (node (ref "SSR_2FG") (pin "8") (pinfunction "O2_8") (pintype "bidirectional"))
    )
    (net (code "26") (name "CH2_PG+") (class "Default")
      (node (ref "PIEZO_HEADER_A1") (pin "32") (pinfunction "32_32") (pintype "passive"))
      (node (ref "SSR_2FG") (pin "6") (pinfunction "O2_6") (pintype "bidirectional"))
    )
    (net (code "27") (name "CH2_PH+") (class "Default")
      (node (ref "PIEZO_HEADER_A1") (pin "34") (pinfunction "34_34") (pintype "passive"))
      (node (ref "SSR_2HJ") (pin "8") (pinfunction "O2_8") (pintype "bidirectional"))
    )
    (net (code "28") (name "CH2_PJ+") (class "Default")
      (node (ref "PIEZO_HEADER_A1") (pin "36") (pinfunction "36_36") (pintype "passive"))
      (node (ref "SSR_2HJ") (pin "6") (pinfunction "O2_6") (pintype "bidirectional"))
    )
    (net (code "29") (name "CH3_I+") (class "Default")
      (node (ref "AUDIO_IN") (pin "21") (pinfunction "21_21") (pintype "passive"))
    )
    (net (code "30") (name "CH3_I-") (class "Default")
      (node (ref "AUDIO_IN") (pin "9") (pinfunction "9_9") (pintype "passive"))
    )
    (net (code "31") (name "CH4_I+") (class "Default")
      (node (ref "AUDIO_IN") (pin "7") (pinfunction "7_7") (pintype "passive"))
    )
    (net (code "32") (name "CH4_I-") (class "Default")
      (node (ref "AUDIO_IN") (pin "20") (pinfunction "20_20") (pintype "passive"))
    )
    (net (code "33") (name "CH5_I+") (class "Default")
      (node (ref "AUDIO_IN") (pin "18") (pinfunction "18_18") (pintype "passive"))
    )
    (net (code "34") (name "CH5_I-") (class "Default")
      (node (ref "AUDIO_IN") (pin "6") (pinfunction "6_6") (pintype "passive"))
    )
    (net (code "35") (name "CH6_I+") (class "Default")
      (node (ref "AUDIO_IN") (pin "4") (pinfunction "4_4") (pintype "passive"))
    )
    (net (code "36") (name "CH6_I-") (class "Default")
      (node (ref "AUDIO_IN") (pin "17") (pinfunction "17_17") (pintype "passive"))
    )
    (net (code "37") (name "CH7_I+") (class "Default")
      (node (ref "AUDIO_IN") (pin "15") (pinfunction "15_15") (pintype "passive"))
    )
    (net (code "38") (name "CH7_I-") (class "Default")
      (node (ref "AUDIO_IN") (pin "3") (pinfunction "3_3") (pintype "passive"))
    )
    (net (code "39") (name "CH8_I+") (class "Default")
      (node (ref "AUDIO_IN") (pin "1") (pinfunction "1_1") (pintype "passive"))
    )
    (net (code "40") (name "CH8_I-") (class "Default")
      (node (ref "AUDIO_IN") (pin "14") (pinfunction "14_14") (pintype "passive"))
    )
    (net (code "41") (name "GND") (class "Default")
      (node (ref "AUDIO_IN") (pin "11") (pinfunction "11_11") (pintype "passive"))
      (node (ref "AUDIO_IN") (pin "16") (pinfunction "16_16") (pintype "passive"))
      (node (ref "AUDIO_IN") (pin "19") (pinfunction "19_19") (pintype "passive"))
      (node (ref "AUDIO_IN") (pin "2") (pinfunction "2_2") (pintype "passive"))
      (node (ref "AUDIO_IN") (pin "22") (pinfunction "22_22") (pintype "passive"))
      (node (ref "AUDIO_IN") (pin "25") (pinfunction "25_25") (pintype "passive"))
      (node (ref "AUDIO_IN") (pin "5") (pinfunction "5_5") (pintype "passive"))
      (node (ref "AUDIO_IN") (pin "8") (pinfunction "8_8") (pintype "passive"))
      (node (ref "GND_LIFT") (pin "1") (pinfunction "T1A_1") (pintype "bidirectional"))
      (node (ref "GND_LIFT") (pin "6") (pinfunction "T2A_6") (pintype "bidirectional"))
    )
    (net (code "42") (name "INT0") (class "Default")
      (node (ref "JP2") (pin "7") (pinfunction "7_7") (pintype "passive"))
    )
    (net (code "43") (name "INT1") (class "Default")
      (node (ref "JP2") (pin "8") (pinfunction "8_8") (pintype "passive"))
    )
    (net (code "44") (name "LED1") (class "Default")
      (node (ref "JP2") (pin "4") (pinfunction "4_4") (pintype "passive"))
      (node (ref "RLED1") (pin "1") (pinfunction "1_1") (pintype "passive"))
    )
    (net (code "45") (name "LED2") (class "Default")
      (node (ref "JP2") (pin "5") (pinfunction "5_5") (pintype "passive"))
      (node (ref "RLED2") (pin "1") (pinfunction "1_1") (pintype "passive"))
    )
    (net (code "46") (name "LED3") (class "Default")
      (node (ref "JP2") (pin "6") (pinfunction "6_6") (pintype "passive"))
      (node (ref "RLED3") (pin "1") (pinfunction "1_1") (pintype "passive"))
    )
    (net (code "47") (name "Net-(DRV1-FB)") (class "Default")
      (node (ref "DRV1") (pin "3") (pinfunction "FB_3") (pintype "bidirectional"))
      (node (ref "RVBST1-1") (pin "1") (pinfunction "1_1") (pintype "passive"))
      (node (ref "RVBST1-2") (pin "2") (pinfunction "2_2") (pintype "passive"))
    )
    (net (code "48") (name "Net-(DRV1-PVDD)") (class "Default")
      (node (ref "CVBST1") (pin "1") (pinfunction "1_1") (pintype "passive"))
      (node (ref "DRV1") (pin "10") (pinfunction "VBST_10") (pintype "bidirectional"))
      (node (ref "DRV1") (pin "11") (pinfunction "VBST_11") (pintype "bidirectional"))
      (node (ref "DRV1") (pin "12") (pinfunction "PVDD_12") (pintype "bidirectional"))
      (node (ref "RVBST1-1") (pin "2") (pinfunction "2_2") (pintype "passive"))
    )
    (net (code "49") (name "Net-(DRV1-REXT)") (class "Default")
      (node (ref "DRV1") (pin "15") (pinfunction "REXT_15") (pintype "bidirectional"))
      (node (ref "REXT1") (pin "2") (pinfunction "2_2") (pintype "passive"))
    )
    (net (code "50") (name "Net-(DRV1-SW-Pad7)") (class "Default")
      (node (ref "DRV1") (pin "7") (pinfunction "SW_7") (pintype "bidirectional"))
      (node (ref "DRV1") (pin "8") (pinfunction "SW_8") (pintype "bidirectional"))
      (node (ref "L1") (pin "1") (pinfunction "1_1") (pintype "passive"))
    )
    (net (code "51") (name "Net-(DRV1-VPUMP)") (class "Default")
      (node (ref "CPUMP1") (pin "1") (pinfunction "1_1") (pintype "passive"))
      (node (ref "DRV1") (pin "1") (pinfunction "VPUMP_1") (pintype "bidirectional"))
    )
    (net (code "52") (name "Net-(DRV1-VREG)") (class "Default")
      (node (ref "CVREG1") (pin "1") (pinfunction "1_1") (pintype "passive"))
      (node (ref "DRV1") (pin "20") (pinfunction "VREG_20") (pintype "bidirectional"))
    )
    (net (code "53") (name "Net-(DRV2-FB)") (class "Default")
      (node (ref "DRV2") (pin "3") (pinfunction "FB_3") (pintype "bidirectional"))
      (node (ref "RVBST2-1") (pin "1") (pinfunction "1_1") (pintype "passive"))
      (node (ref "RVBST2-2") (pin "2") (pinfunction "2_2") (pintype "passive"))
    )
    (net (code "54") (name "Net-(DRV2-PVDD)") (class "Default")
      (node (ref "CVBST2") (pin "1") (pinfunction "1_1") (pintype "passive"))
      (node (ref "DRV2") (pin "10") (pinfunction "VBST_10") (pintype "bidirectional"))
      (node (ref "DRV2") (pin "11") (pinfunction "VBST_11") (pintype "bidirectional"))
      (node (ref "DRV2") (pin "12") (pinfunction "PVDD_12") (pintype "bidirectional"))
      (node (ref "RVBST2-1") (pin "2") (pinfunction "2_2") (pintype "passive"))
    )
    (net (code "55") (name "Net-(DRV2-REXT)") (class "Default")
      (node (ref "DRV2") (pin "15") (pinfunction "REXT_15") (pintype "bidirectional"))
      (node (ref "REXT2") (pin "2") (pinfunction "2_2") (pintype "passive"))
    )
    (net (code "56") (name "Net-(DRV2-SW-Pad7)") (class "Default")
      (node (ref "DRV2") (pin "7") (pinfunction "SW_7") (pintype "bidirectional"))
      (node (ref "DRV2") (pin "8") (pinfunction "SW_8") (pintype "bidirectional"))
      (node (ref "L2") (pin "1") (pinfunction "1_1") (pintype "passive"))
    )
    (net (code "57") (name "Net-(DRV2-VPUMP)") (class "Default")
      (node (ref "CPUMP2") (pin "1") (pinfunction "1_1") (pintype "passive"))
      (node (ref "DRV2") (pin "1") (pinfunction "VPUMP_1") (pintype "bidirectional"))
    )
    (net (code "58") (name "Net-(DRV2-VREG)") (class "Default")
      (node (ref "CVREG2") (pin "1") (pinfunction "1_1") (pintype "passive"))
      (node (ref "DRV2") (pin "20") (pinfunction "VREG_20") (pintype "bidirectional"))
    )
    (net (code "59") (name "Net-(GND_LIFT-P1)") (class "Default")
      (node (ref "GND_LIFT") (pin "2") (pinfunction "P1_2") (pintype "bidirectional"))
      (node (ref "GND_LIFT") (pin "5") (pinfunction "P2_5") (pintype "bidirectional"))
      (node (ref "R_GND1") (pin "2") (pinfunction "2_2") (pintype "passive"))
      (node (ref "R_GND2") (pin "1") (pinfunction "1_1") (pintype "passive"))
    )
    (net (code "60") (name "Net-(LED1-PadC)") (class "Default")
      (node (ref "LED1") (pin "C") (pinfunction "C_C") (pintype "passive"))
      (node (ref "RLED1") (pin "2") (pinfunction "2_2") (pintype "passive"))
    )
    (net (code "61") (name "Net-(LED2-PadC)") (class "Default")
      (node (ref "LED2") (pin "C") (pinfunction "C_C") (pintype "passive"))
      (node (ref "RLED2") (pin "2") (pinfunction "2_2") (pintype "passive"))
    )
    (net (code "62") (name "Net-(LED3-PadC)") (class "Default")
      (node (ref "LED3") (pin "C") (pinfunction "C_C") (pintype "passive"))
      (node (ref "RLED3") (pin "2") (pinfunction "2_2") (pintype "passive"))
    )
    (net (code "63") (name "Net-(LED_SUP-PadA)") (class "Default")
      (node (ref "LED_SUP") (pin "A") (pinfunction "A_A") (pintype "passive"))
      (node (ref "RLED_SUP") (pin "1") (pinfunction "1_1") (pintype "passive"))
    )
    (net (code "64") (name "Net-(SSR_1ABA-I+)") (class "Default")
      (node (ref "R_1A") (pin "1") (pinfunction "1_1") (pintype "passive"))
      (node (ref "SSR_1AB") (pin "1") (pinfunction "I+_1") (pintype "bidirectional"))
    )
    (net (code "65") (name "Net-(SSR_1ABB-I+)") (class "Default")
      (node (ref "R_1B") (pin "1") (pinfunction "1_1") (pintype "passive"))
      (node (ref "SSR_1AB") (pin "3") (pinfunction "I+_3") (pintype "bidirectional"))
    )
    (net (code "66") (name "Net-(SSR_1CDA-I+)") (class "Default")
      (node (ref "R_1C") (pin "1") (pinfunction "1_1") (pintype "passive"))
      (node (ref "SSR_1CD") (pin "1") (pinfunction "I+_1") (pintype "bidirectional"))
    )
    (net (code "67") (name "Net-(SSR_1CDB-I+)") (class "Default")
      (node (ref "R_1D") (pin "1") (pinfunction "1_1") (pintype "passive"))
      (node (ref "SSR_1CD") (pin "3") (pinfunction "I+_3") (pintype "bidirectional"))
    )
    (net (code "68") (name "Net-(SSR_1EFA-I+)") (class "Default")
      (node (ref "R_1E") (pin "1") (pinfunction "1_1") (pintype "passive"))
      (node (ref "SSR_1EF") (pin "1") (pinfunction "I+_1") (pintype "bidirectional"))
    )
    (net (code "69") (name "Net-(SSR_1EFB-I+)") (class "Default")
      (node (ref "R_1F") (pin "1") (pinfunction "1_1") (pintype "passive"))
      (node (ref "SSR_1EF") (pin "3") (pinfunction "I+_3") (pintype "bidirectional"))
    )
    (net (code "70") (name "Net-(SSR_1GHA-I+)") (class "Default")
      (node (ref "R_1G") (pin "1") (pinfunction "1_1") (pintype "passive"))
      (node (ref "SSR_1GH") (pin "1") (pinfunction "I+_1") (pintype "bidirectional"))
    )
    (net (code "71") (name "Net-(SSR_1GHB-I+)") (class "Default")
      (node (ref "R_1H") (pin "1") (pinfunction "1_1") (pintype "passive"))
      (node (ref "SSR_1GH") (pin "3") (pinfunction "I+_3") (pintype "bidirectional"))
    )
    (net (code "72") (name "Net-(SSR_1J/2AA-I+)") (class "Default")
      (node (ref "R_1J") (pin "1") (pinfunction "1_1") (pintype "passive"))
      (node (ref "SSR_1J/2A") (pin "1") (pinfunction "I+_1") (pintype "bidirectional"))
    )
    (net (code "73") (name "Net-(SSR_1J/2AB-I+)") (class "Default")
      (node (ref "R_2A") (pin "1") (pinfunction "1_1") (pintype "passive"))
      (node (ref "SSR_1J/2A") (pin "3") (pinfunction "I+_3") (pintype "bidirectional"))
    )
    (net (code "74") (name "Net-(SSR_2BCA-I+)") (class "Default")
      (node (ref "R_2B") (pin "1") (pinfunction "1_1") (pintype "passive"))
      (node (ref "SSR_2BC") (pin "1") (pinfunction "I+_1") (pintype "bidirectional"))
    )
    (net (code "75") (name "Net-(SSR_2BCB-I+)") (class "Default")
      (node (ref "R_2C") (pin "1") (pinfunction "1_1") (pintype "passive"))
      (node (ref "SSR_2BC") (pin "3") (pinfunction "I+_3") (pintype "bidirectional"))
    )
    (net (code "76") (name "Net-(SSR_2DEA-I+)") (class "Default")
      (node (ref "R_2D") (pin "1") (pinfunction "1_1") (pintype "passive"))
      (node (ref "SSR_2DE") (pin "1") (pinfunction "I+_1") (pintype "bidirectional"))
    )
    (net (code "77") (name "Net-(SSR_2DEB-I+)") (class "Default")
      (node (ref "R_2E") (pin "1") (pinfunction "1_1") (pintype "passive"))
      (node (ref "SSR_2DE") (pin "3") (pinfunction "I+_3") (pintype "bidirectional"))
    )
    (net (code "78") (name "Net-(SSR_2FGA-I+)") (class "Default")
      (node (ref "R_2F") (pin "1") (pinfunction "1_1") (pintype "passive"))
      (node (ref "SSR_2FG") (pin "1") (pinfunction "I+_1") (pintype "bidirectional"))
    )
    (net (code "79") (name "Net-(SSR_2FGB-I+)") (class "Default")
      (node (ref "R_2G") (pin "1") (pinfunction "1_1") (pintype "passive"))
      (node (ref "SSR_2FG") (pin "3") (pinfunction "I+_3") (pintype "bidirectional"))
    )
    (net (code "80") (name "Net-(SSR_2HJA-I+)") (class "Default")
      (node (ref "R_2H") (pin "1") (pinfunction "1_1") (pintype "passive"))
      (node (ref "SSR_2HJ") (pin "1") (pinfunction "I+_1") (pintype "bidirectional"))
    )
    (net (code "81") (name "Net-(SSR_2HJB-I+)") (class "Default")
      (node (ref "R_2J") (pin "1") (pinfunction "1_1") (pintype "passive"))
      (node (ref "SSR_2HJ") (pin "3") (pinfunction "I+_3") (pintype "bidirectional"))
    )
    (net (code "82") (name "REG_CLR") (class "Default")
      (node (ref "JP1") (pin "1") (pinfunction "1_1") (pintype "passive"))
      (node (ref "R_CLR") (pin "1") (pinfunction "1_1") (pintype "passive"))
      (node (ref "SHIFTER1") (pin "10") (pinfunction "~{SCLR}_10") (pintype "bidirectional"))
      (node (ref "SHIFTER2") (pin "10") (pinfunction "~{SCLR}_10") (pintype "bidirectional"))
      (node (ref "SHIFTER3") (pin "10") (pinfunction "~{SCLR}_10") (pintype "bidirectional"))
    )
    (net (code "83") (name "REG_LOAD") (class "Default")
      (node (ref "JP1") (pin "3") (pinfunction "3_3") (pintype "passive"))
      (node (ref "R_LOAD") (pin "2") (pinfunction "2_2") (pintype "passive"))
      (node (ref "SHIFTER1") (pin "12") (pinfunction "RCK_12") (pintype "bidirectional"))
      (node (ref "SHIFTER2") (pin "12") (pinfunction "RCK_12") (pintype "bidirectional"))
      (node (ref "SHIFTER3") (pin "12") (pinfunction "RCK_12") (pintype "bidirectional"))
    )
    (net (code "84") (name "REG_OE") (class "Default")
      (node (ref "JP1") (pin "4") (pinfunction "4_4") (pintype "passive"))
      (node (ref "R_OE") (pin "1") (pinfunction "1_1") (pintype "passive"))
      (node (ref "SHIFTER1") (pin "13") (pinfunction "~{G}_13") (pintype "bidirectional"))
      (node (ref "SHIFTER2") (pin "13") (pinfunction "~{G}_13") (pintype "bidirectional"))
      (node (ref "SHIFTER3") (pin "13") (pinfunction "~{G}_13") (pintype "bidirectional"))
    )
    (net (code "85") (name "SPI_MOSI") (class "Default")
      (node (ref "JP1") (pin "5") (pinfunction "5_5") (pintype "passive"))
      (node (ref "SHIFTER1") (pin "14") (pinfunction "SI_14") (pintype "bidirectional"))
    )
    (net (code "86") (name "SPI_SCLK") (class "Default")
      (node (ref "JP1") (pin "2") (pinfunction "2_2") (pintype "passive"))
      (node (ref "SHIFTER1") (pin "11") (pinfunction "SCK_11") (pintype "bidirectional"))
      (node (ref "SHIFTER2") (pin "11") (pinfunction "SCK_11") (pintype "bidirectional"))
      (node (ref "SHIFTER3") (pin "11") (pinfunction "SCK_11") (pintype "bidirectional"))
    )
    (net (code "87") (name "SPI_SO1-SI2") (class "Default")
      (node (ref "SHIFTER1") (pin "9") (pinfunction "SO_9") (pintype "bidirectional"))
      (node (ref "SHIFTER2") (pin "14") (pinfunction "SI_14") (pintype "bidirectional"))
    )
    (net (code "88") (name "SPI_SO2-SI3") (class "Default")
      (node (ref "SHIFTER2") (pin "9") (pinfunction "SO_9") (pintype "bidirectional"))
      (node (ref "SHIFTER3") (pin "14") (pinfunction "SI_14") (pintype "bidirectional"))
    )
    (net (code "89") (name "SW-1A") (class "Default")
      (node (ref "SHIFTER1") (pin "15") (pinfunction "Q0_15") (pintype "bidirectional"))
      (node (ref "SSR_1AB") (pin "2") (pinfunction "I-_2") (pintype "bidirectional"))
    )
    (net (code "90") (name "SW-1B") (class "Default")
      (node (ref "SHIFTER1") (pin "1") (pinfunction "Q1_1") (pintype "bidirectional"))
      (node (ref "SSR_1AB") (pin "4") (pinfunction "I-_4") (pintype "bidirectional"))
    )
    (net (code "91") (name "SW-1C") (class "Default")
      (node (ref "SHIFTER1") (pin "2") (pinfunction "Q2_2") (pintype "bidirectional"))
      (node (ref "SSR_1CD") (pin "2") (pinfunction "I-_2") (pintype "bidirectional"))
    )
    (net (code "92") (name "SW-1D") (class "Default")
      (node (ref "SHIFTER1") (pin "3") (pinfunction "Q3_3") (pintype "bidirectional"))
      (node (ref "SSR_1CD") (pin "4") (pinfunction "I-_4") (pintype "bidirectional"))
    )
    (net (code "93") (name "SW-1E") (class "Default")
      (node (ref "SHIFTER1") (pin "4") (pinfunction "Q4_4") (pintype "bidirectional"))
      (node (ref "SSR_1EF") (pin "2") (pinfunction "I-_2") (pintype "bidirectional"))
    )
    (net (code "94") (name "SW-1F") (class "Default")
      (node (ref "SHIFTER1") (pin "5") (pinfunction "Q5_5") (pintype "bidirectional"))
      (node (ref "SSR_1EF") (pin "4") (pinfunction "I-_4") (pintype "bidirectional"))
    )
    (net (code "95") (name "SW-1G") (class "Default")
      (node (ref "SHIFTER1") (pin "6") (pinfunction "Q6_6") (pintype "bidirectional"))
      (node (ref "SSR_1GH") (pin "2") (pinfunction "I-_2") (pintype "bidirectional"))
    )
    (net (code "96") (name "SW-1H") (class "Default")
      (node (ref "SHIFTER1") (pin "7") (pinfunction "Q7_7") (pintype "bidirectional"))
      (node (ref "SSR_1GH") (pin "4") (pinfunction "I-_4") (pintype "bidirectional"))
    )
    (net (code "97") (name "SW-1J") (class "Default")
      (node (ref "SHIFTER2") (pin "15") (pinfunction "Q0_15") (pintype "bidirectional"))
      (node (ref "SSR_1J/2A") (pin "2") (pinfunction "I-_2") (pintype "bidirectional"))
    )
    (net (code "98") (name "SW-2A") (class "Default")
      (node (ref "SHIFTER2") (pin "1") (pinfunction "Q1_1") (pintype "bidirectional"))
      (node (ref "SSR_1J/2A") (pin "4") (pinfunction "I-_4") (pintype "bidirectional"))
    )
    (net (code "99") (name "SW-2B") (class "Default")
      (node (ref "SHIFTER2") (pin "2") (pinfunction "Q2_2") (pintype "bidirectional"))
      (node (ref "SSR_2BC") (pin "2") (pinfunction "I-_2") (pintype "bidirectional"))
    )
    (net (code "100") (name "SW-2C") (class "Default")
      (node (ref "SHIFTER2") (pin "3") (pinfunction "Q3_3") (pintype "bidirectional"))
      (node (ref "SSR_2BC") (pin "4") (pinfunction "I-_4") (pintype "bidirectional"))
    )
    (net (code "101") (name "SW-2D") (class "Default")
      (node (ref "SHIFTER2") (pin "4") (pinfunction "Q4_4") (pintype "bidirectional"))
      (node (ref "SSR_2DE") (pin "2") (pinfunction "I-_2") (pintype "bidirectional"))
    )
    (net (code "102") (name "SW-2E") (class "Default")
      (node (ref "SHIFTER2") (pin "5") (pinfunction "Q5_5") (pintype "bidirectional"))
      (node (ref "SSR_2DE") (pin "4") (pinfunction "I-_4") (pintype "bidirectional"))
    )
    (net (code "103") (name "SW-2F") (class "Default")
      (node (ref "SHIFTER2") (pin "6") (pinfunction "Q6_6") (pintype "bidirectional"))
      (node (ref "SSR_2FG") (pin "2") (pinfunction "I-_2") (pintype "bidirectional"))
    )
    (net (code "104") (name "SW-2G") (class "Default")
      (node (ref "SHIFTER2") (pin "7") (pinfunction "Q7_7") (pintype "bidirectional"))
      (node (ref "SSR_2FG") (pin "4") (pinfunction "I-_4") (pintype "bidirectional"))
    )
    (net (code "105") (name "SW-2H") (class "Default")
      (node (ref "SHIFTER3") (pin "15") (pinfunction "Q0_15") (pintype "bidirectional"))
      (node (ref "SSR_2HJ") (pin "2") (pinfunction "I-_2") (pintype "bidirectional"))
    )
    (net (code "106") (name "SW-2J") (class "Default")
      (node (ref "SHIFTER3") (pin "1") (pinfunction "Q1_1") (pintype "bidirectional"))
      (node (ref "SSR_2HJ") (pin "4") (pinfunction "I-_4") (pintype "bidirectional"))
    )
    (net (code "107") (name "TWI_SCL") (class "Default")
      (node (ref "DRV1") (pin "18") (pinfunction "SCL_18") (pintype "bidirectional"))
      (node (ref "DRV2") (pin "18") (pinfunction "SCL_18") (pintype "bidirectional"))
      (node (ref "JP1") (pin "6") (pinfunction "6_6") (pintype "passive"))
      (node (ref "R_SCL") (pin "1") (pinfunction "1_1") (pintype "passive"))
    )
    (net (code "108") (name "TWI_SDA") (class "Default")
      (node (ref "DRV1") (pin "19") (pinfunction "SDA_19") (pintype "bidirectional"))
      (node (ref "DRV2") (pin "19") (pinfunction "SDA_19") (pintype "bidirectional"))
      (node (ref "JP1") (pin "7") (pinfunction "7_7") (pintype "passive"))
      (node (ref "R_SDA") (pin "1") (pinfunction "1_1") (pintype "passive"))
    )
    (net (code "109") (name "UART_RXD") (class "Default")
      (node (ref "JP2") (pin "3") (pinfunction "3_3") (pintype "passive"))
    )
    (net (code "110") (name "UART_TXD") (class "Default")
      (node (ref "JP2") (pin "2") (pinfunction "2_2") (pintype "passive"))
    )
    (net (code "111") (name "UART_XCK") (class "Default")
      (node (ref "JP2") (pin "1") (pinfunction "1_1") (pintype "passive"))
    )
    (net (code "112") (name "unconnected-(AUDIO_IN-Pad13)") (class "Default")
      (node (ref "AUDIO_IN") (pin "13") (pinfunction "13_13") (pintype "passive"))
    )
    (net (code "113") (name "unconnected-(GND_LIFT-T1B-Pad3)") (class "Default")
      (node (ref "GND_LIFT") (pin "3") (pinfunction "T1B_3") (pintype "bidirectional"))
    )
    (net (code "114") (name "unconnected-(GND_LIFT-T2B-Pad4)") (class "Default")
      (node (ref "GND_LIFT") (pin "4") (pinfunction "T2B_4") (pintype "bidirectional"))
    )
    (net (code "115") (name "unconnected-(SHIFTER3A-Q2-Pad2)") (class "Default")
      (node (ref "SHIFTER3") (pin "2") (pinfunction "Q2_2") (pintype "bidirectional"))
    )
    (net (code "116") (name "unconnected-(SHIFTER3A-Q3-Pad3)") (class "Default")
      (node (ref "SHIFTER3") (pin "3") (pinfunction "Q3_3") (pintype "bidirectional"))
    )
    (net (code "117") (name "unconnected-(SHIFTER3A-Q4-Pad4)") (class "Default")
      (node (ref "SHIFTER3") (pin "4") (pinfunction "Q4_4") (pintype "bidirectional"))
    )
    (net (code "118") (name "unconnected-(SHIFTER3A-Q5-Pad5)") (class "Default")
      (node (ref "SHIFTER3") (pin "5") (pinfunction "Q5_5") (pintype "bidirectional"))
    )
    (net (code "119") (name "unconnected-(SHIFTER3A-Q6-Pad6)") (class "Default")
      (node (ref "SHIFTER3") (pin "6") (pinfunction "Q6_6") (pintype "bidirectional"))
    )
    (net (code "120") (name "unconnected-(SHIFTER3A-Q7-Pad7)") (class "Default")
      (node (ref "SHIFTER3") (pin "7") (pinfunction "Q7_7") (pintype "bidirectional"))
    )
    (net (code "121") (name "unconnected-(SHIFTER3A-SO-Pad9)") (class "Default")
      (node (ref "SHIFTER3") (pin "9") (pinfunction "SO_9") (pintype "bidirectional"))
    )
  )
)
